# cave.net
KiCad netlist of a schematic drawn in EAGLE
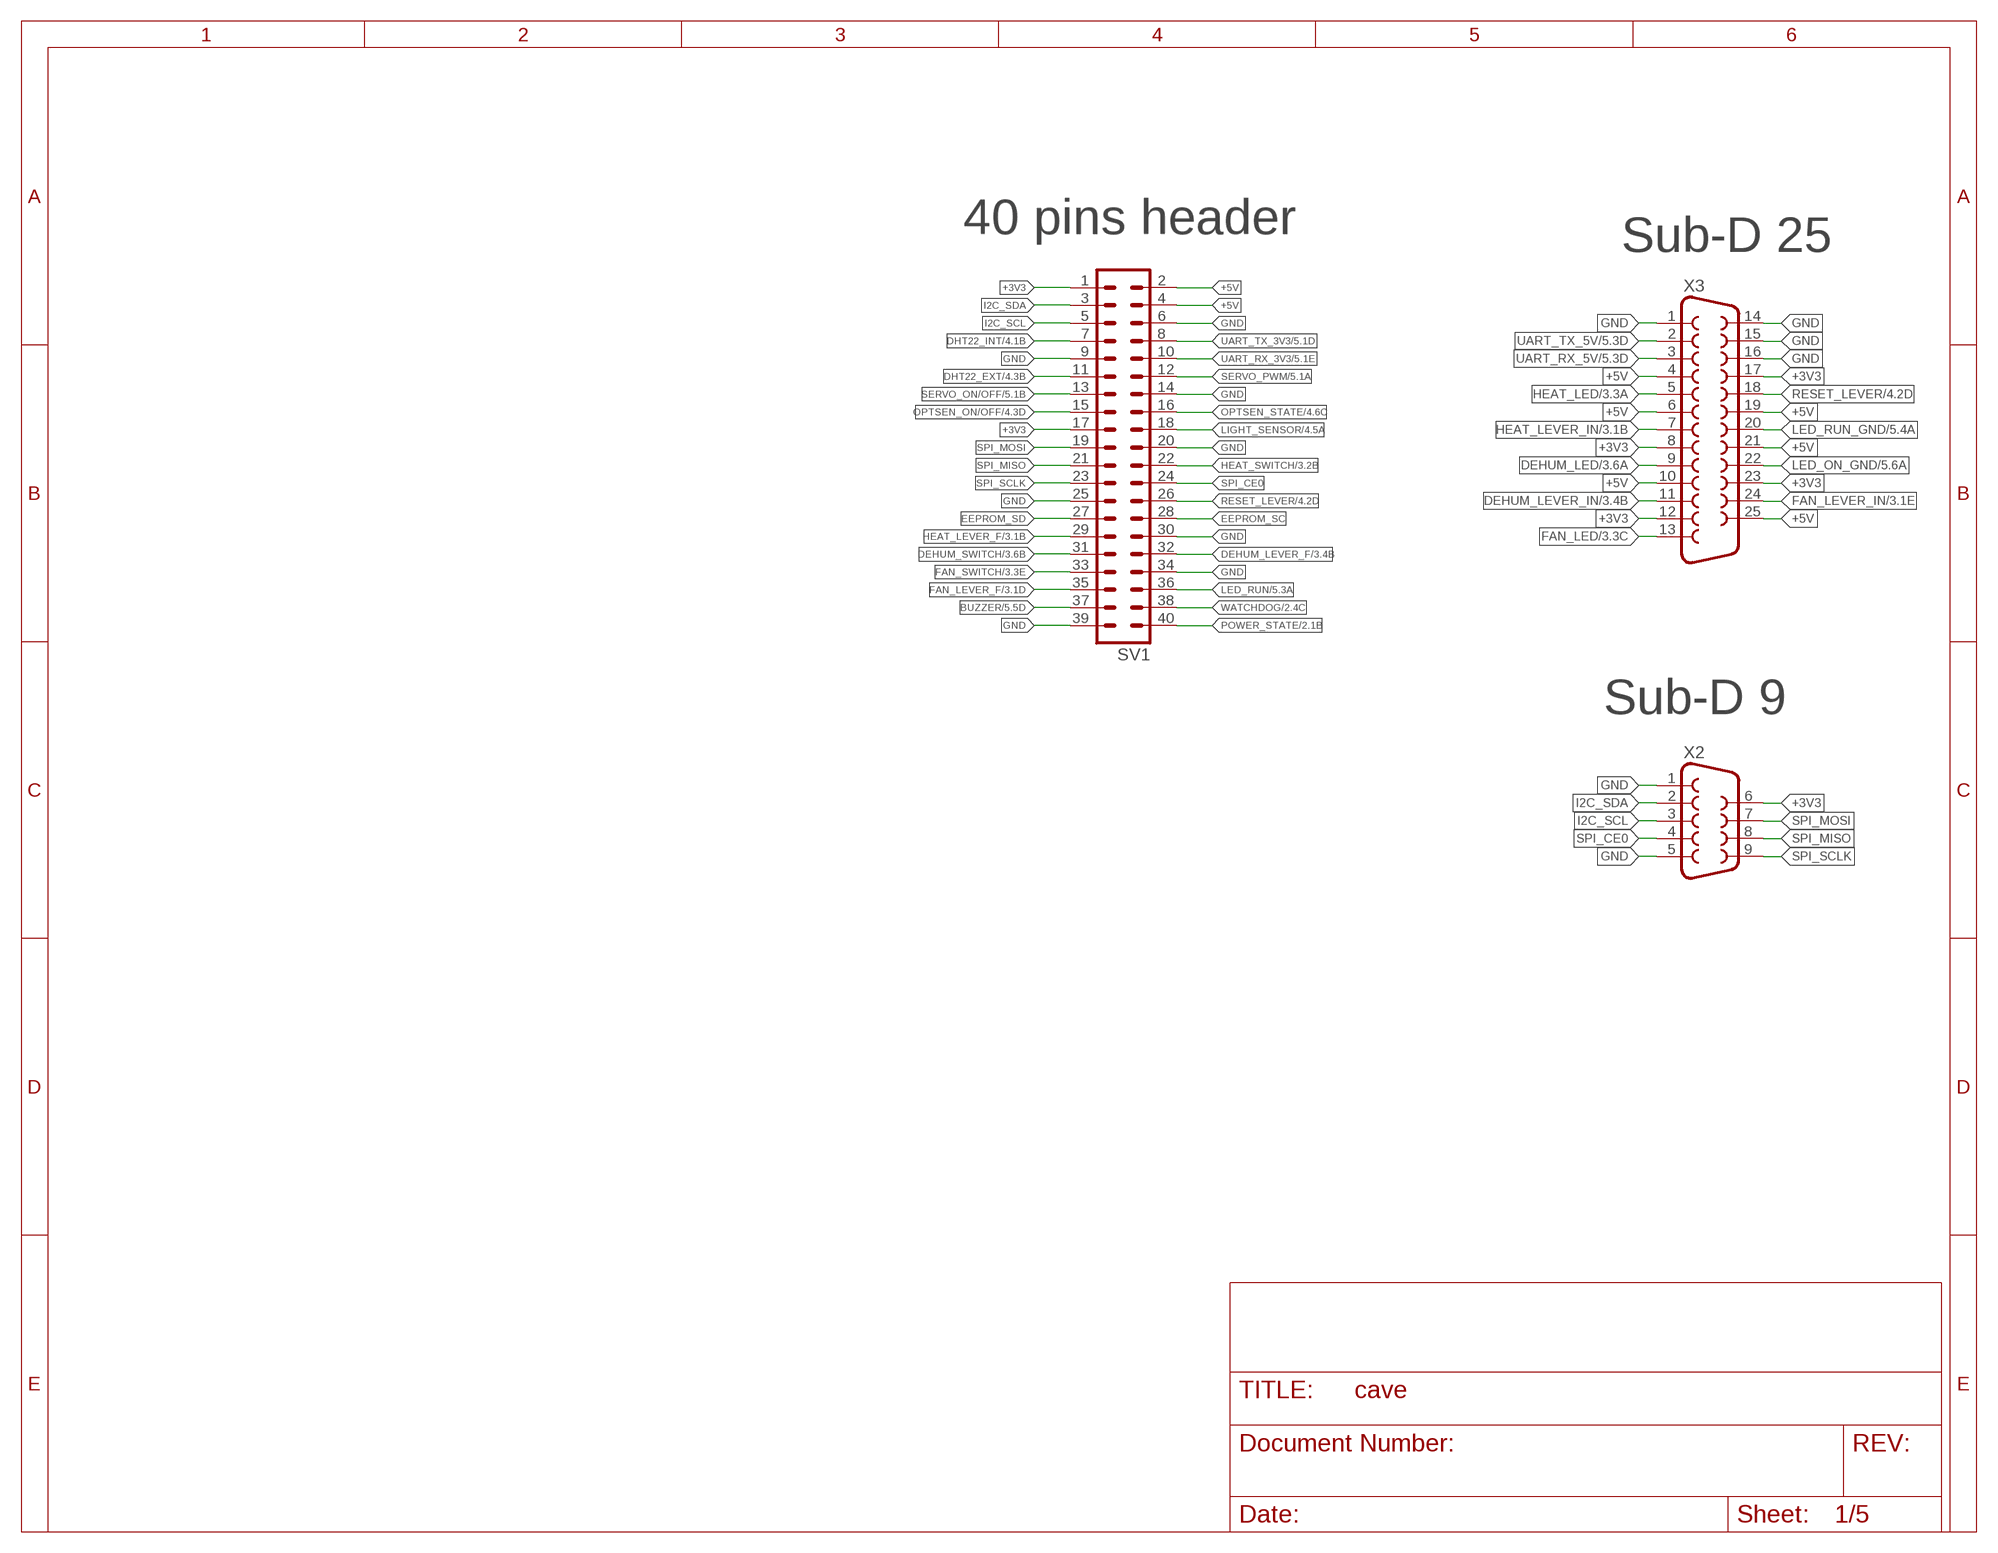
[diagram p0: schematic, sheet 1]
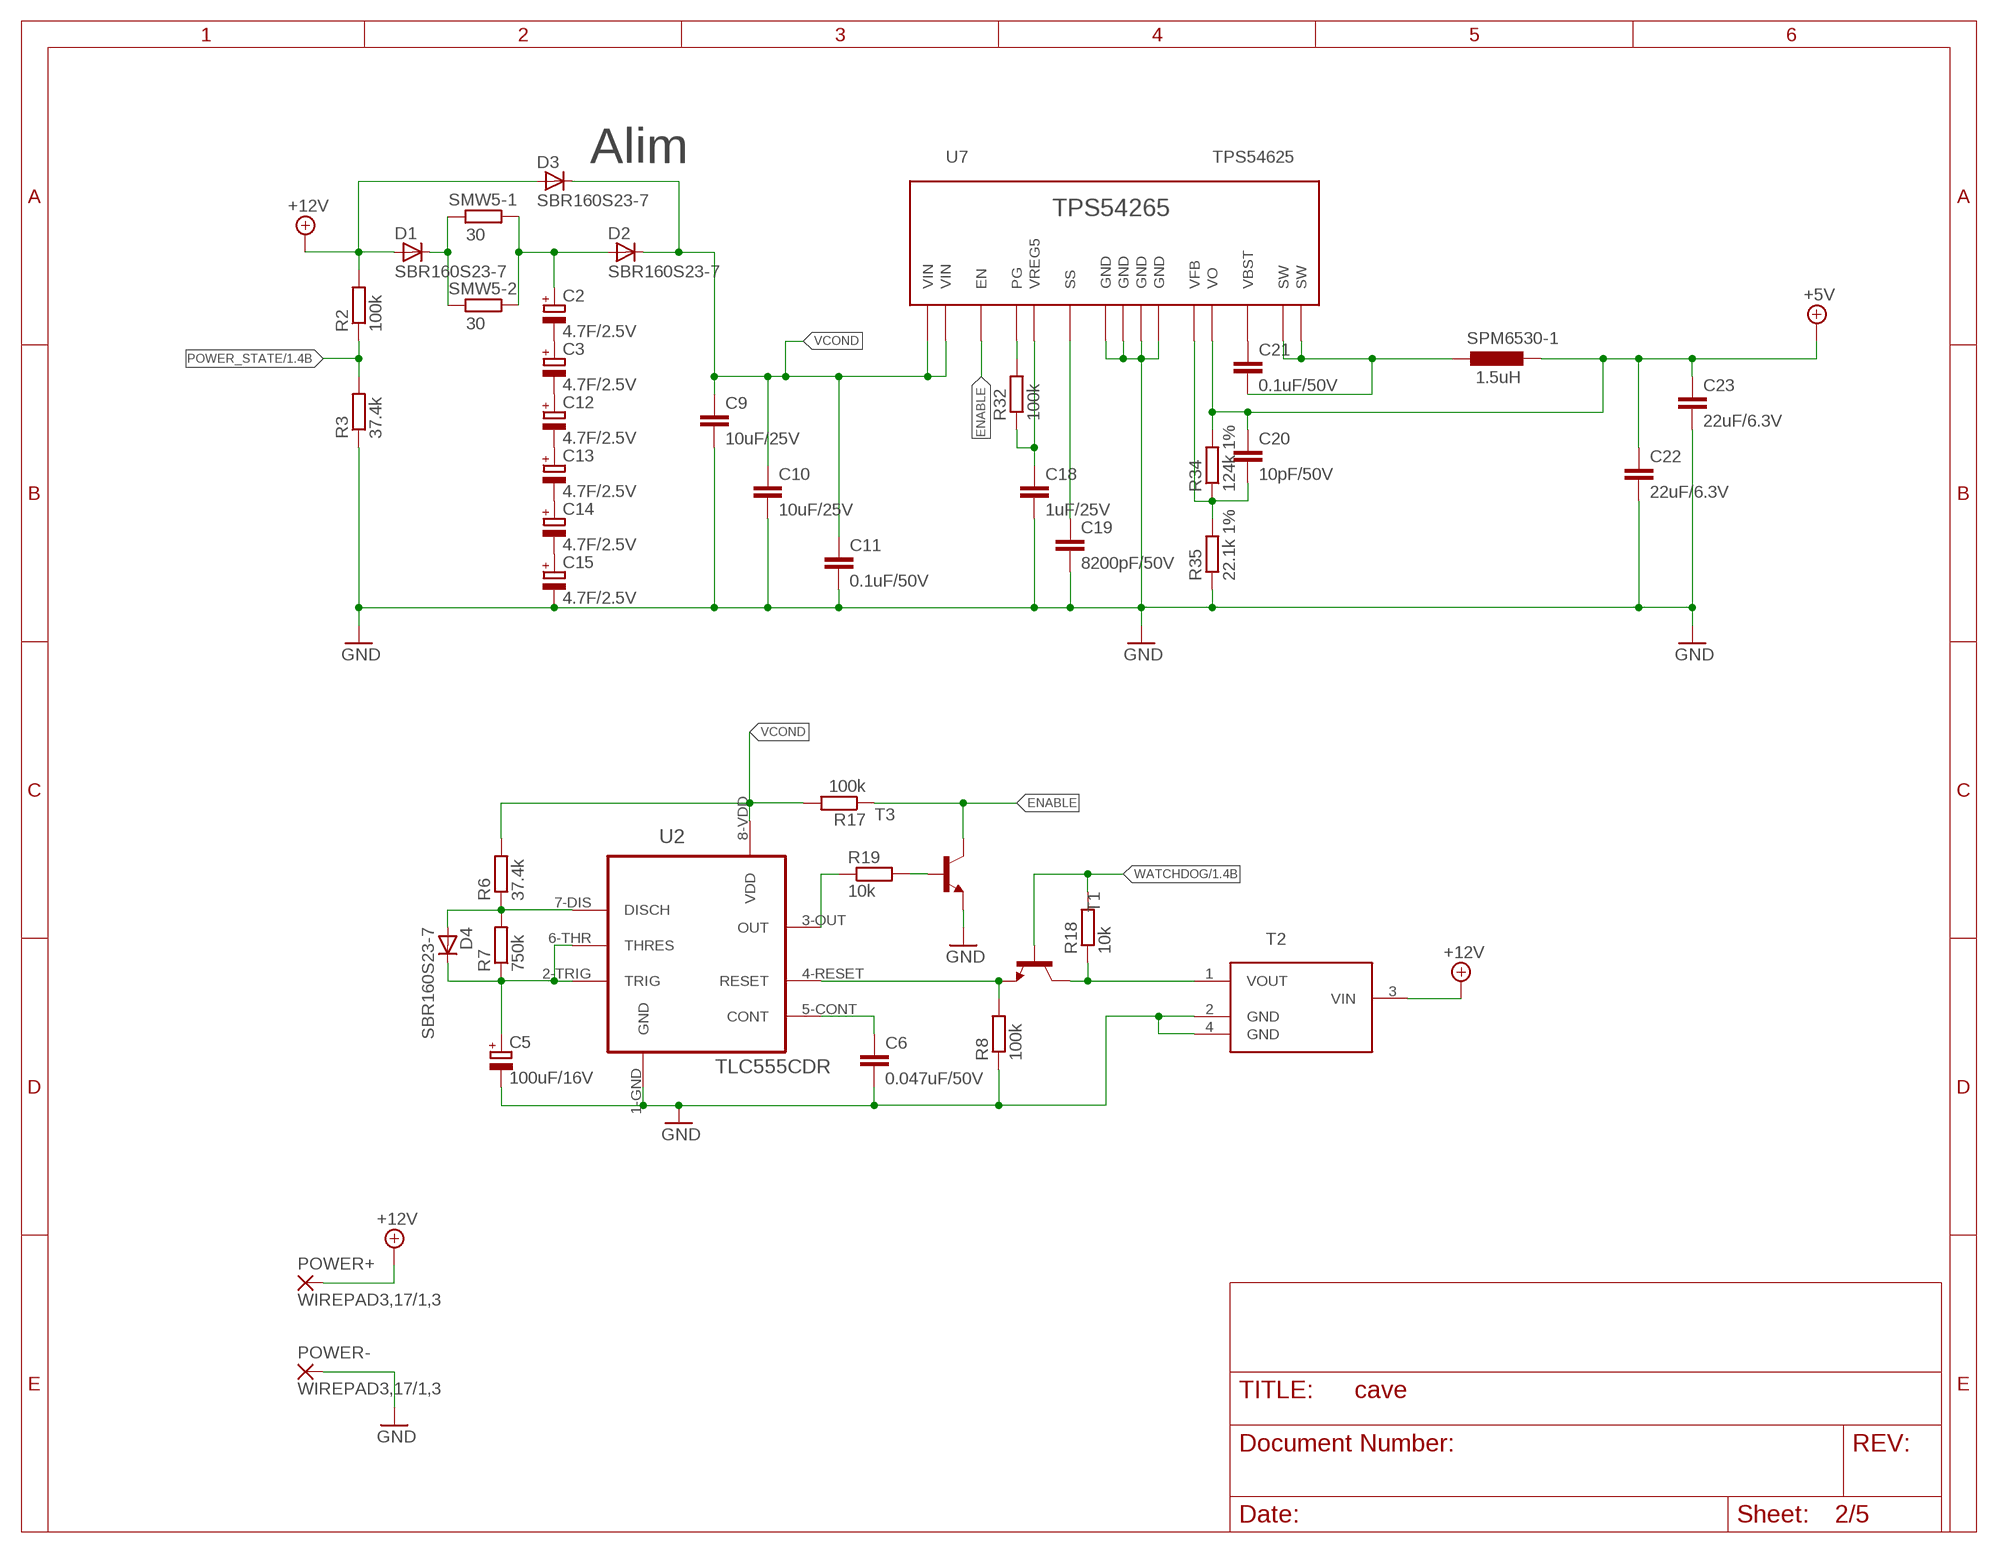
[diagram p1: schematic, sheet 2]
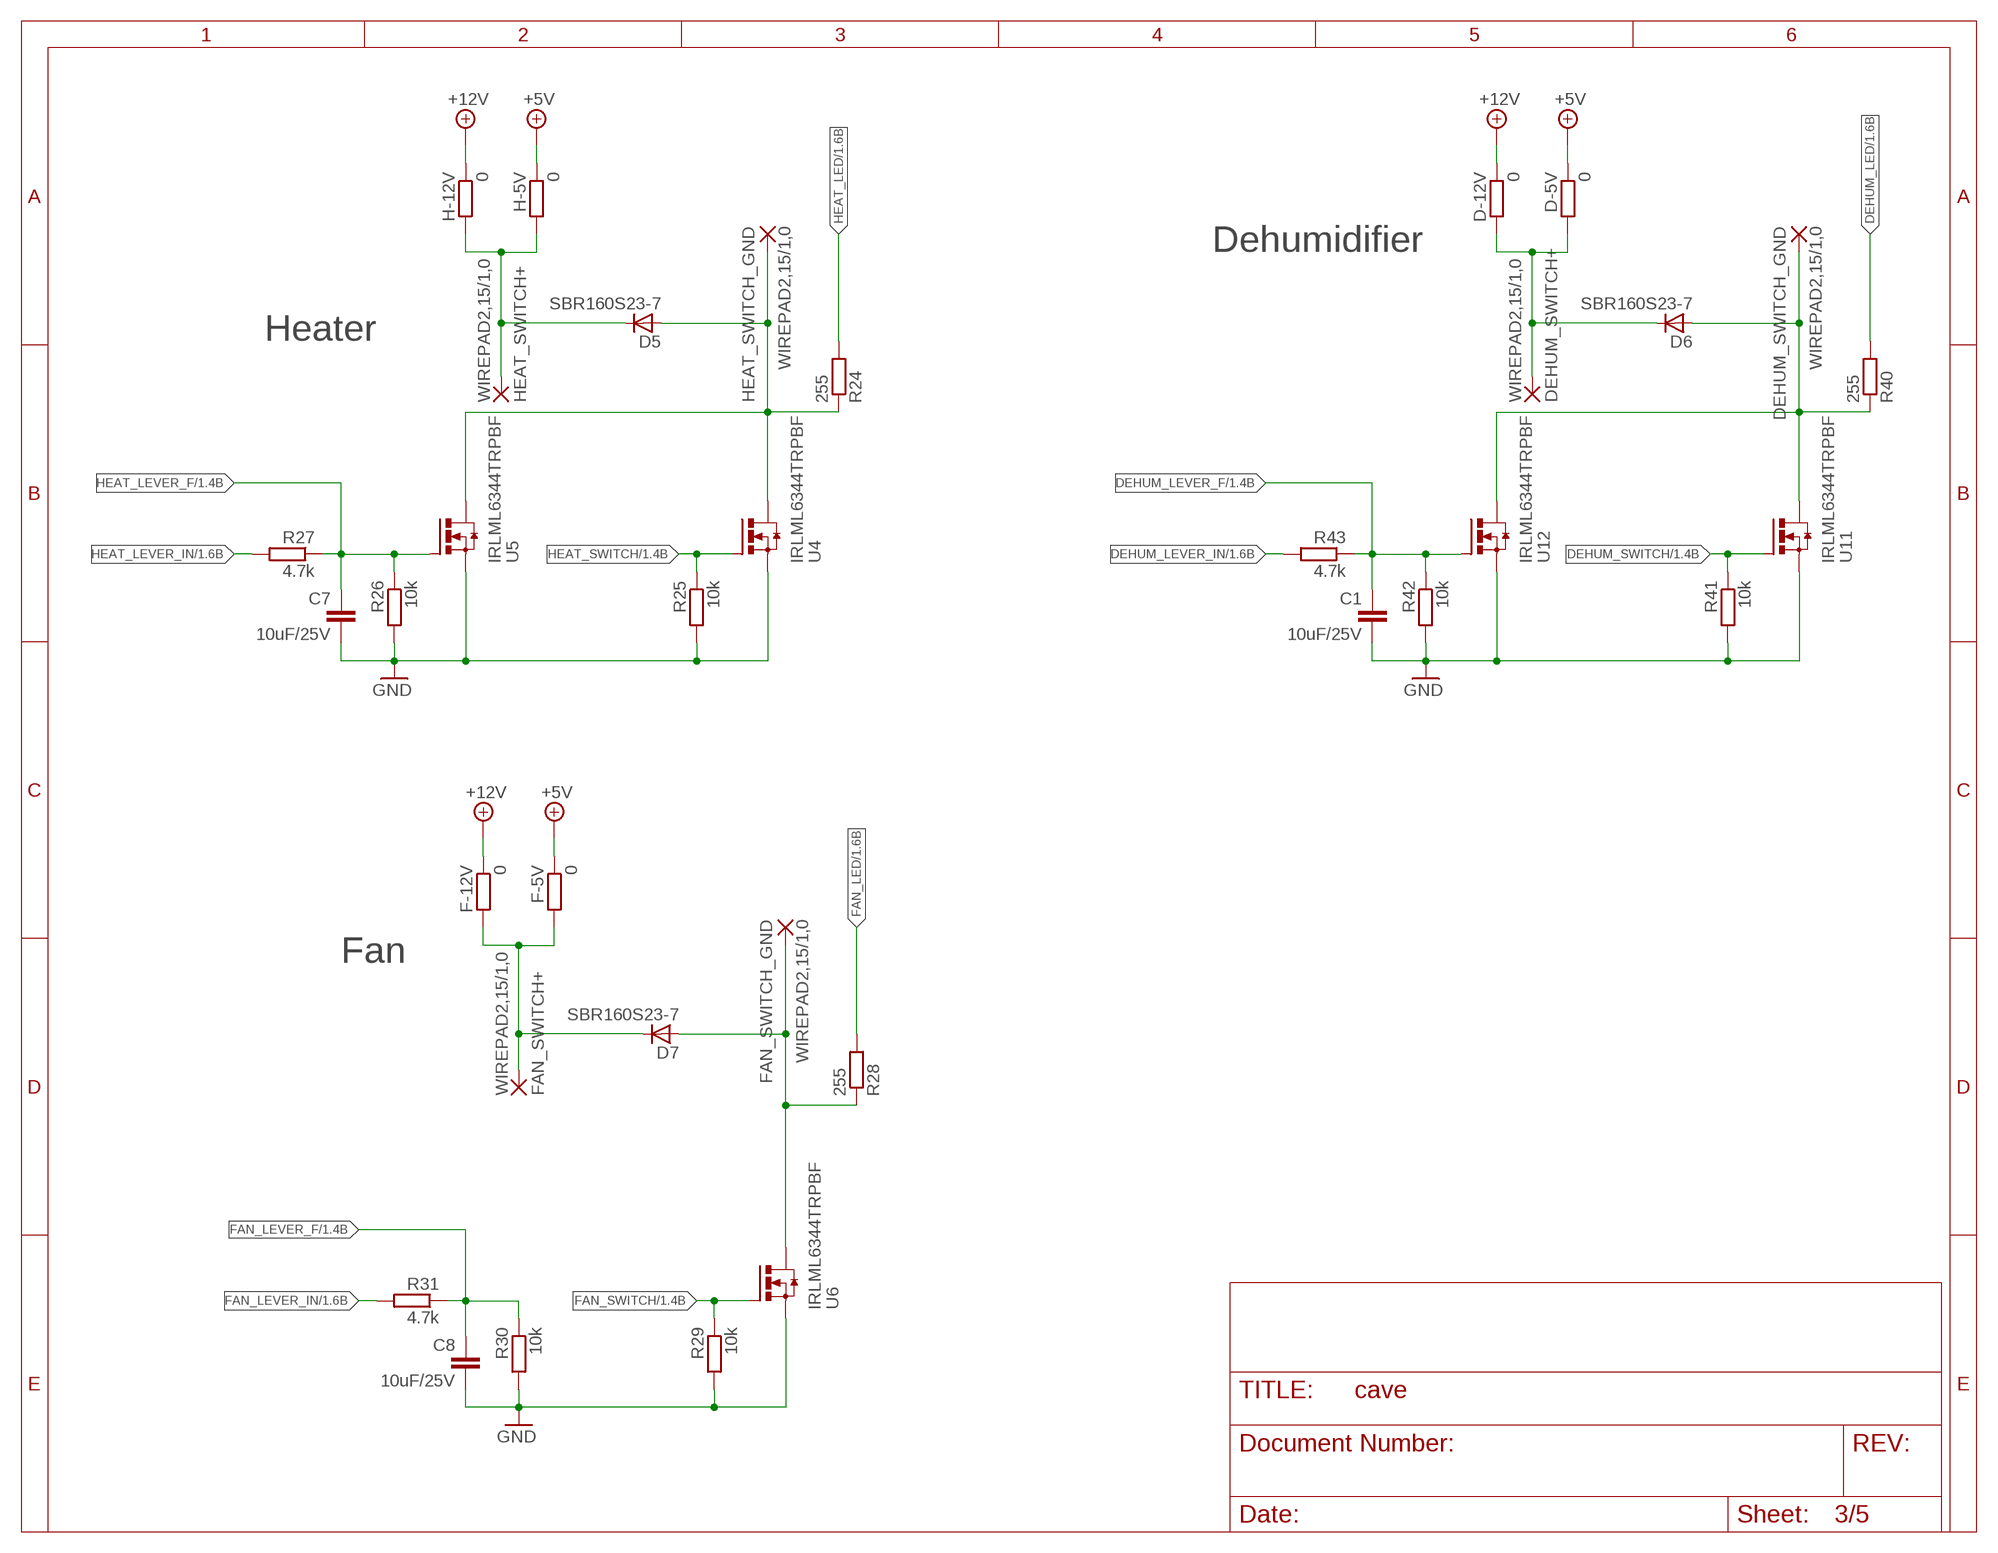
[diagram p2: schematic, sheet 3]
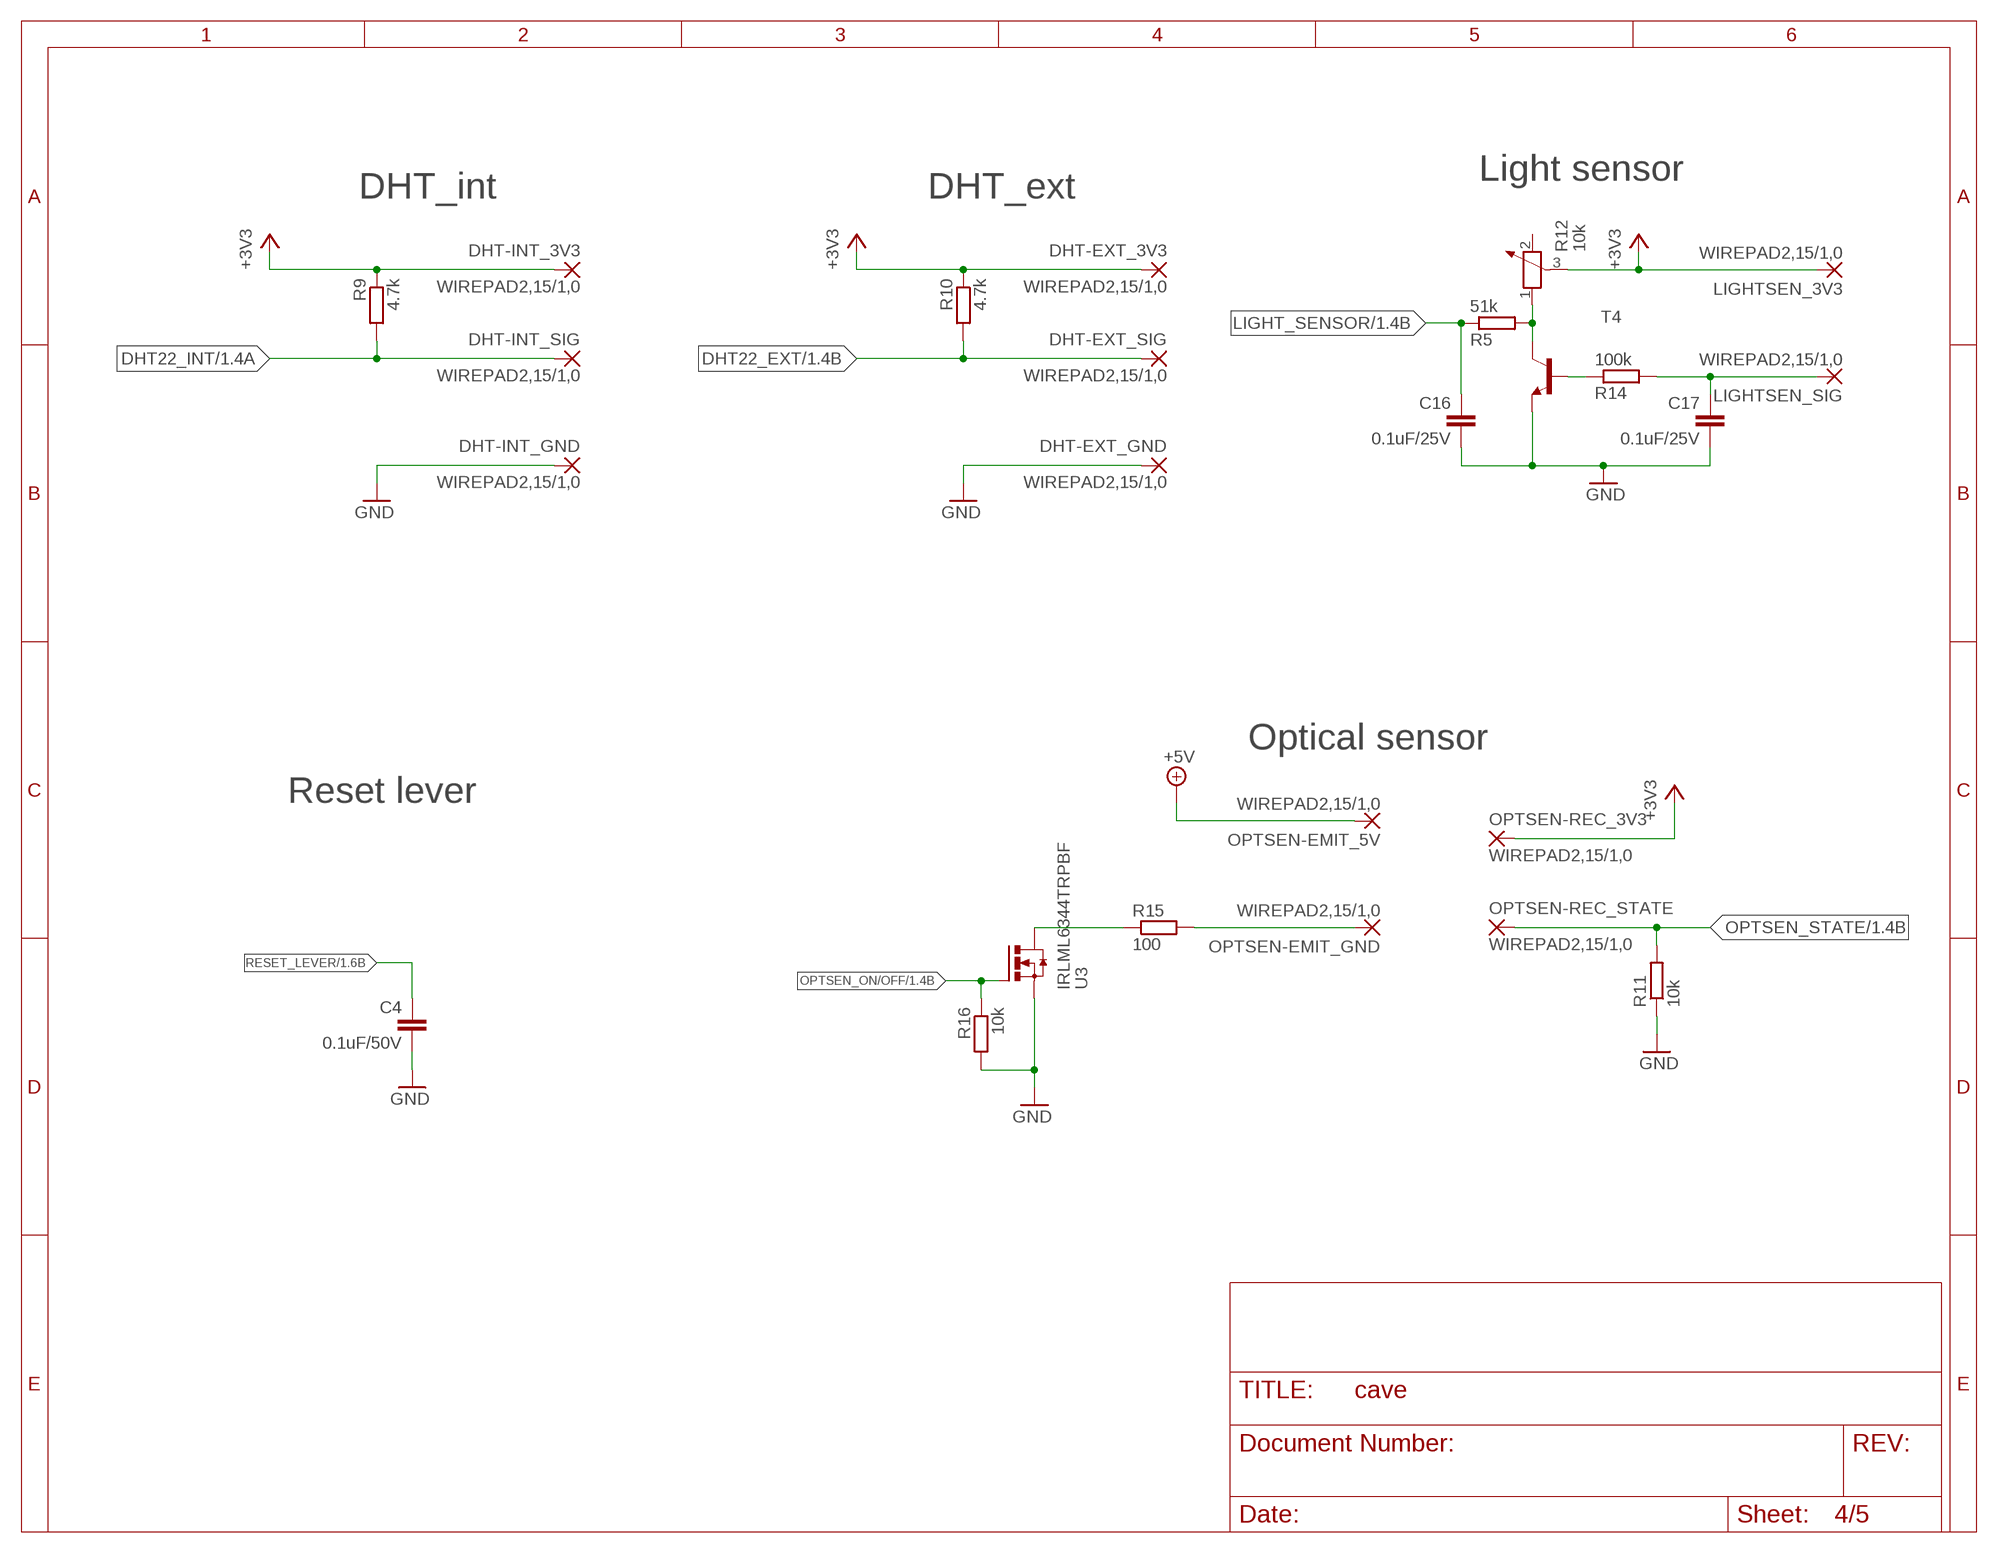
[diagram p3: schematic, sheet 4]
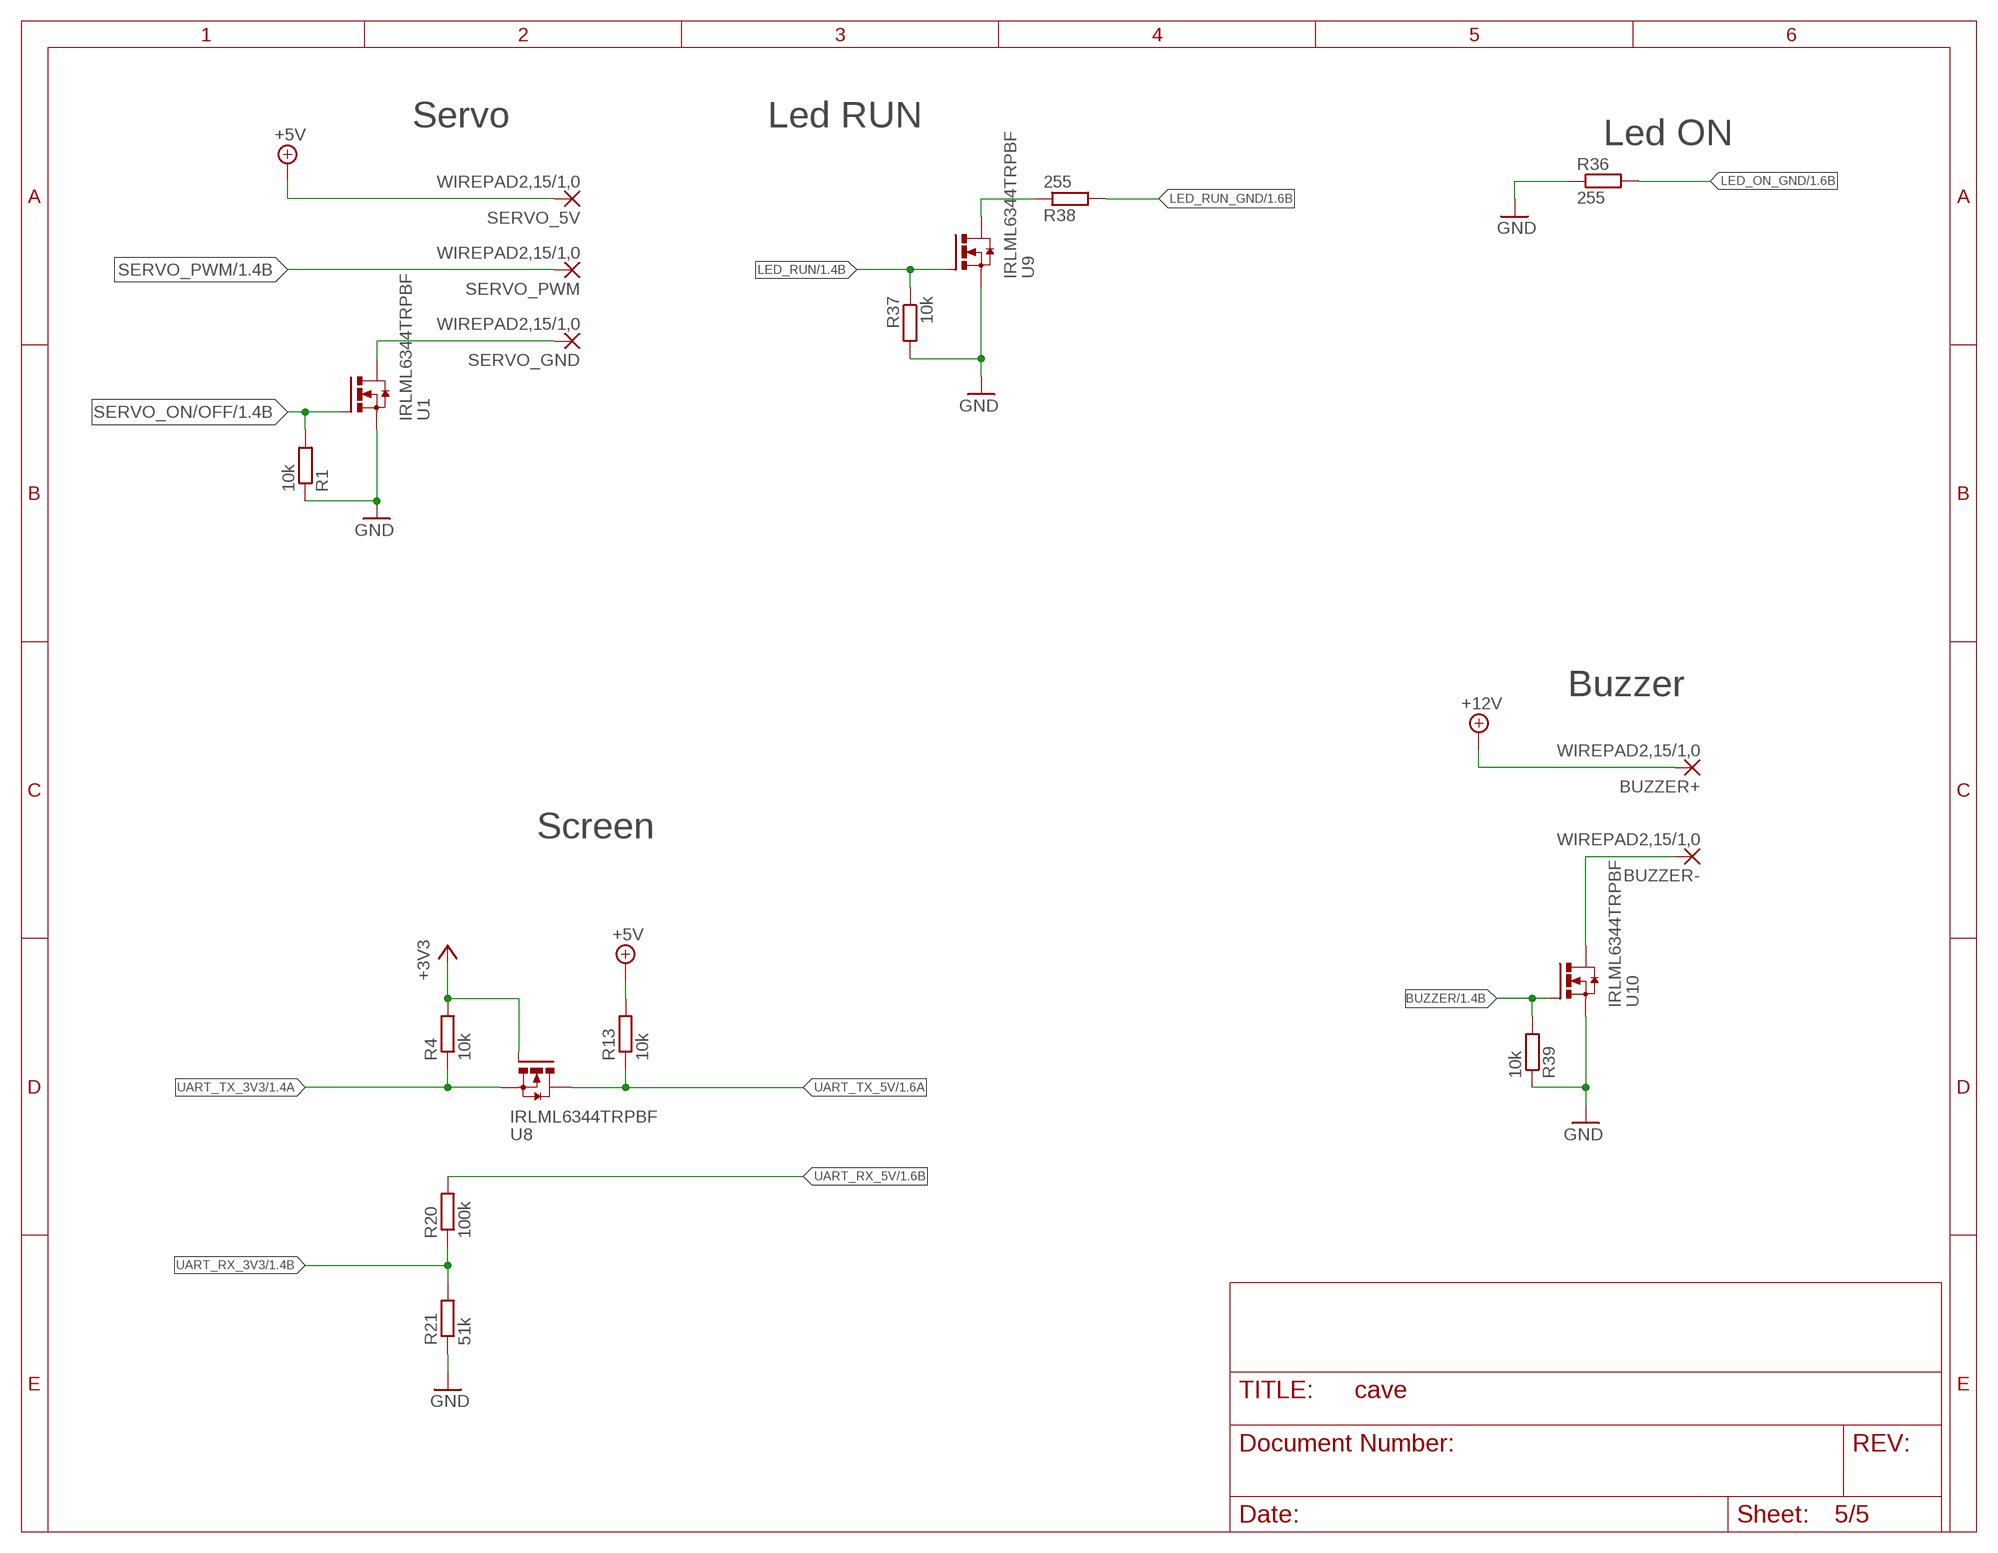
[diagram p4: schematic, sheet 5]

(export (version "E")
  (design (tool "Eeschema 10.0.6"))
  (components
    (comp (ref "C2")
      (value "4.7F/2.5V")
      (footprint "eagle-import:E5-10,5")
      (libsource (lib "eagle-import") (part "CPOL-EUE5-10.5"))
    )
    (comp (ref "C3")
      (value "4.7F/2.5V")
      (footprint "eagle-import:E5-10,5")
      (libsource (lib "eagle-import") (part "CPOL-EUE5-10.5"))
    )
    (comp (ref "C5")
      (value "100uF/16V")
      (footprint "eagle-import:D_7343-31W")
      (libsource (lib "eagle-import") (part "resistor_CPOL-EUD/7343-31W"))
    )
    (comp (ref "C6")
      (value "0.047uF/50V")
      (footprint "eagle-import:C0603")
      (libsource (lib "eagle-import") (part "C-EUC0603"))
    )
    (comp (ref "C9")
      (value "10uF/25V")
      (footprint "eagle-import:C0805")
      (libsource (lib "eagle-import") (part "C-EUC0805"))
    )
    (comp (ref "C10")
      (value "10uF/25V")
      (footprint "eagle-import:C0805")
      (libsource (lib "eagle-import") (part "C-EUC0805"))
    )
    (comp (ref "C11")
      (value "0.1uF/50V")
      (footprint "eagle-import:C0603")
      (libsource (lib "eagle-import") (part "C-EUC0603"))
    )
    (comp (ref "C12")
      (value "4.7F/2.5V")
      (footprint "eagle-import:E5-10,5")
      (libsource (lib "eagle-import") (part "CPOL-EUE5-10.5"))
    )
    (comp (ref "C13")
      (value "4.7F/2.5V")
      (footprint "eagle-import:E5-10,5")
      (libsource (lib "eagle-import") (part "CPOL-EUE5-10.5"))
    )
    (comp (ref "C14")
      (value "4.7F/2.5V")
      (footprint "eagle-import:E5-10,5")
      (libsource (lib "eagle-import") (part "CPOL-EUE5-10.5"))
    )
    (comp (ref "C15")
      (value "4.7F/2.5V")
      (footprint "eagle-import:E5-10,5")
      (libsource (lib "eagle-import") (part "CPOL-EUE5-10.5"))
    )
    (comp (ref "C18")
      (value "1uF/25V")
      (footprint "eagle-import:C0603")
      (libsource (lib "eagle-import") (part "C-EUC0603"))
    )
    (comp (ref "C19")
      (value "8200pF/50V")
      (footprint "eagle-import:C0603")
      (libsource (lib "eagle-import") (part "C-EUC0603"))
    )
    (comp (ref "C20")
      (value "10pF/50V")
      (footprint "eagle-import:C0603")
      (libsource (lib "eagle-import") (part "C-EUC0603"))
    )
    (comp (ref "C21")
      (value "0.1uF/50V")
      (footprint "eagle-import:C0603")
      (libsource (lib "eagle-import") (part "C-EUC0603"))
    )
    (comp (ref "C22")
      (value "22uF/6.3V")
      (footprint "eagle-import:C0805")
      (libsource (lib "eagle-import") (part "C-EUC0805"))
    )
    (comp (ref "C23")
      (value "22uF/6.3V")
      (footprint "eagle-import:C0805")
      (libsource (lib "eagle-import") (part "C-EUC0805"))
    )
    (comp (ref "D1")
      (value "SBR160S23-7")
      (footprint "eagle-import:SOT23")
      (libsource (lib "eagle-import") (part "D-A1-C3"))
    )
    (comp (ref "D2")
      (value "SBR160S23-7")
      (footprint "eagle-import:SOT23")
      (libsource (lib "eagle-import") (part "D-A1-C3"))
    )
    (comp (ref "D3")
      (value "SBR160S23-7")
      (footprint "eagle-import:SOT23")
      (libsource (lib "eagle-import") (part "D-A1-C3"))
    )
    (comp (ref "D4")
      (value "SBR160S23-7")
      (footprint "eagle-import:SOT23")
      (libsource (lib "eagle-import") (part "D-A1-C3"))
    )
    (comp (ref "POWER+")
      (value "WIREPAD3,17/1,3")
      (footprint "eagle-import:3,17_1,3")
      (libsource (lib "eagle-import") (part "WIREPAD3,17/1,3"))
    )
    (comp (ref "POWER-")
      (value "WIREPAD3,17/1,3")
      (footprint "eagle-import:3,17_1,3")
      (libsource (lib "eagle-import") (part "WIREPAD3,17/1,3"))
    )
    (comp (ref "R2")
      (value "100k")
      (footprint "eagle-import:R0603")
      (libsource (lib "eagle-import") (part "R-EU_R0603"))
    )
    (comp (ref "R3")
      (value "37.4k")
      (footprint "eagle-import:R0603")
      (libsource (lib "eagle-import") (part "R-EU_R0603"))
    )
    (comp (ref "R6")
      (value "37.4k")
      (footprint "eagle-import:R0603")
      (libsource (lib "eagle-import") (part "R-EU_R0603"))
    )
    (comp (ref "R7")
      (value "750k")
      (footprint "eagle-import:R0603")
      (libsource (lib "eagle-import") (part "R-EU_R0603"))
    )
    (comp (ref "R8")
      (value "100k")
      (footprint "eagle-import:R0603")
      (libsource (lib "eagle-import") (part "R-EU_R0603"))
    )
    (comp (ref "R17")
      (value "100k")
      (footprint "eagle-import:R0603")
      (libsource (lib "eagle-import") (part "R-EU_R0603"))
    )
    (comp (ref "R18")
      (value "10k")
      (footprint "eagle-import:R0603")
      (libsource (lib "eagle-import") (part "R-EU_R0603"))
    )
    (comp (ref "R19")
      (value "10k")
      (footprint "eagle-import:R0603")
      (libsource (lib "eagle-import") (part "R-EU_R0603"))
    )
    (comp (ref "R32")
      (value "100k")
      (footprint "eagle-import:R0603")
      (libsource (lib "eagle-import") (part "R-EU_R0603"))
    )
    (comp (ref "R34")
      (value "124k 1%")
      (footprint "eagle-import:R0603")
      (libsource (lib "eagle-import") (part "R-EU_R0603"))
    )
    (comp (ref "R35")
      (value "22.1k 1%")
      (footprint "eagle-import:R0603")
      (libsource (lib "eagle-import") (part "R-EU_R0603"))
    )
    (comp (ref "SMW5-1")
      (value "30")
      (footprint "eagle-import:SM_5")
      (libsource (lib "eagle-import") (part "SMW530RJT"))
    )
    (comp (ref "SMW5-2")
      (value "30")
      (footprint "eagle-import:SM_5")
      (libsource (lib "eagle-import") (part "SMW530RJT"))
    )
    (comp (ref "SPM6530-1")
      (value "1.5uH")
      (footprint "eagle-import:6530")
      (libsource (lib "eagle-import") (part "SPM6530"))
    )
    (comp (ref "T1")
      (value "MMBT2369LT1-NPN-SOT23-BEC")
      (footprint "eagle-import:SOT23-BEC")
      (libsource (lib "eagle-import") (part "-NPN-SOT23-BECMMBT2369LT1"))
    )
    (comp (ref "T2")
      (value "L78L33ACUTR")
      (footprint "eagle-import:SOT150P400X160-4N")
      (libsource (lib "eagle-import") (part "L78L33ACUTR"))
    )
    (comp (ref "T3")
      (value "MMBT2369LT1-NPN-SOT23-BEC")
      (footprint "eagle-import:SOT23-BEC")
      (libsource (lib "eagle-import") (part "-NPN-SOT23-BECMMBT2369LT1"))
    )
    (comp (ref "U2")
      (value "TLC555CDR")
      (footprint "eagle-import:SOIC127P600X175-8N")
      (libsource (lib "eagle-import") (part "TLC555CDR"))
    )
    (comp (ref "U7")
      (value "TPS54625")
      (footprint "eagle-import:HTSSOP-14")
      (libsource (lib "eagle-import") (part "TPS54625"))
    )
    (comp (ref "C4")
      (value "0.1uF/50V")
      (footprint "eagle-import:C0603")
      (libsource (lib "eagle-import") (part "C-EUC0603"))
    )
    (comp (ref "C16")
      (value "0.1uF/25V")
      (footprint "eagle-import:C0603")
      (libsource (lib "eagle-import") (part "C-EUC0603"))
    )
    (comp (ref "C17")
      (value "0.1uF/25V")
      (footprint "eagle-import:C0603")
      (libsource (lib "eagle-import") (part "C-EUC0603"))
    )
    (comp (ref "DHT-EXT_3V3")
      (value "WIREPAD2,15/1,0")
      (footprint "eagle-import:2,15_1,0")
      (libsource (lib "eagle-import") (part "WIREPAD2,15/1,0"))
    )
    (comp (ref "DHT-EXT_GND")
      (value "WIREPAD2,15/1,0")
      (footprint "eagle-import:2,15_1,0")
      (libsource (lib "eagle-import") (part "WIREPAD2,15/1,0"))
    )
    (comp (ref "DHT-EXT_SIG")
      (value "WIREPAD2,15/1,0")
      (footprint "eagle-import:2,15_1,0")
      (libsource (lib "eagle-import") (part "WIREPAD2,15/1,0"))
    )
    (comp (ref "DHT-INT_3V3")
      (value "WIREPAD2,15/1,0")
      (footprint "eagle-import:2,15_1,0")
      (libsource (lib "eagle-import") (part "WIREPAD2,15/1,0"))
    )
    (comp (ref "DHT-INT_GND")
      (value "WIREPAD2,15/1,0")
      (footprint "eagle-import:2,15_1,0")
      (libsource (lib "eagle-import") (part "WIREPAD2,15/1,0"))
    )
    (comp (ref "DHT-INT_SIG")
      (value "WIREPAD2,15/1,0")
      (footprint "eagle-import:2,15_1,0")
      (libsource (lib "eagle-import") (part "WIREPAD2,15/1,0"))
    )
    (comp (ref "LIGHTSEN_3V3")
      (value "WIREPAD2,15/1,0")
      (footprint "eagle-import:2,15_1,0")
      (libsource (lib "eagle-import") (part "WIREPAD2,15/1,0"))
    )
    (comp (ref "LIGHTSEN_SIG")
      (value "WIREPAD2,15/1,0")
      (footprint "eagle-import:2,15_1,0")
      (libsource (lib "eagle-import") (part "WIREPAD2,15/1,0"))
    )
    (comp (ref "OPTSEN-EMIT_5V")
      (value "WIREPAD2,15/1,0")
      (footprint "eagle-import:2,15_1,0")
      (libsource (lib "eagle-import") (part "WIREPAD2,15/1,0"))
    )
    (comp (ref "OPTSEN-EMIT_GND")
      (value "WIREPAD2,15/1,0")
      (footprint "eagle-import:2,15_1,0")
      (libsource (lib "eagle-import") (part "WIREPAD2,15/1,0"))
    )
    (comp (ref "OPTSEN-REC_3V3")
      (value "WIREPAD2,15/1,0")
      (footprint "eagle-import:2,15_1,0")
      (libsource (lib "eagle-import") (part "WIREPAD2,15/1,0"))
    )
    (comp (ref "OPTSEN-REC_STATE")
      (value "WIREPAD2,15/1,0")
      (footprint "eagle-import:2,15_1,0")
      (libsource (lib "eagle-import") (part "WIREPAD2,15/1,0"))
    )
    (comp (ref "R5")
      (value "51k")
      (footprint "eagle-import:R0603")
      (libsource (lib "eagle-import") (part "R-EU_R0603"))
    )
    (comp (ref "R9")
      (value "4.7k")
      (footprint "eagle-import:R0603")
      (libsource (lib "eagle-import") (part "R-EU_R0603"))
    )
    (comp (ref "R10")
      (value "4.7k")
      (footprint "eagle-import:R0603")
      (libsource (lib "eagle-import") (part "R-EU_R0603"))
    )
    (comp (ref "R11")
      (value "10k")
      (footprint "eagle-import:R0603")
      (libsource (lib "eagle-import") (part "R-EU_R0603"))
    )
    (comp (ref "R12")
      (value "10k")
      (footprint "eagle-import:PT-SPIN")
      (libsource (lib "eagle-import") (part "POTENTIOMETER_PT_SPIN"))
    )
    (comp (ref "R14")
      (value "100k")
      (footprint "eagle-import:R0603")
      (libsource (lib "eagle-import") (part "R-EU_R0603"))
    )
    (comp (ref "R15")
      (value "100")
      (footprint "eagle-import:R0805")
      (libsource (lib "eagle-import") (part "R-EU_R0805"))
    )
    (comp (ref "R16")
      (value "10k")
      (footprint "eagle-import:R0603")
      (libsource (lib "eagle-import") (part "R-EU_R0603"))
    )
    (comp (ref "T4")
      (value "MMBT2369LT1-NPN-SOT23-BEC")
      (footprint "eagle-import:SOT23-BEC")
      (libsource (lib "eagle-import") (part "-NPN-SOT23-BECMMBT2369LT1"))
    )
    (comp (ref "U3")
      (value "IRLML6344TRPBF")
      (footprint "eagle-import:SOT95P240X112-3N")
      (libsource (lib "eagle-import") (part "IRLML6344TRPBF"))
    )
    (comp (ref "SV1")
      (value "MA20-2")
      (footprint "eagle-import:MA20-2")
      (libsource (lib "eagle-import") (part "MA20-2"))
    )
    (comp (ref "X2")
      (value "F09V")
      (footprint "eagle-import:F09V")
      (libsource (lib "eagle-import") (part "F09V"))
    )
    (comp (ref "X3")
      (value "F25V")
      (footprint "eagle-import:F25V")
      (libsource (lib "eagle-import") (part "F25V"))
    )
    (comp (ref "BUZZER+")
      (value "WIREPAD2,15/1,0")
      (footprint "eagle-import:2,15_1,0")
      (libsource (lib "eagle-import") (part "WIREPAD2,15/1,0"))
    )
    (comp (ref "BUZZER-")
      (value "WIREPAD2,15/1,0")
      (footprint "eagle-import:2,15_1,0")
      (libsource (lib "eagle-import") (part "WIREPAD2,15/1,0"))
    )
    (comp (ref "R1")
      (value "10k")
      (footprint "eagle-import:R0603")
      (libsource (lib "eagle-import") (part "R-EU_R0603"))
    )
    (comp (ref "R4")
      (value "10k")
      (footprint "eagle-import:R0603")
      (libsource (lib "eagle-import") (part "R-EU_R0603"))
    )
    (comp (ref "R13")
      (value "10k")
      (footprint "eagle-import:R0603")
      (libsource (lib "eagle-import") (part "R-EU_R0603"))
    )
    (comp (ref "R20")
      (value "100k")
      (footprint "eagle-import:R0603")
      (libsource (lib "eagle-import") (part "R-EU_R0603"))
    )
    (comp (ref "R21")
      (value "51k")
      (footprint "eagle-import:R0603")
      (libsource (lib "eagle-import") (part "R-EU_R0603"))
    )
    (comp (ref "R36")
      (value "255")
      (footprint "eagle-import:R0805")
      (libsource (lib "eagle-import") (part "R-EU_R0805"))
    )
    (comp (ref "R37")
      (value "10k")
      (footprint "eagle-import:R0603")
      (libsource (lib "eagle-import") (part "R-EU_R0603"))
    )
    (comp (ref "R38")
      (value "255")
      (footprint "eagle-import:R0805")
      (libsource (lib "eagle-import") (part "R-EU_R0805"))
    )
    (comp (ref "R39")
      (value "10k")
      (footprint "eagle-import:R0603")
      (libsource (lib "eagle-import") (part "R-EU_R0603"))
    )
    (comp (ref "SERVO_5V")
      (value "WIREPAD2,15/1,0")
      (footprint "eagle-import:2,15_1,0")
      (libsource (lib "eagle-import") (part "WIREPAD2,15/1,0"))
    )
    (comp (ref "SERVO_GND")
      (value "WIREPAD2,15/1,0")
      (footprint "eagle-import:2,15_1,0")
      (libsource (lib "eagle-import") (part "WIREPAD2,15/1,0"))
    )
    (comp (ref "SERVO_PWM")
      (value "WIREPAD2,15/1,0")
      (footprint "eagle-import:2,15_1,0")
      (libsource (lib "eagle-import") (part "WIREPAD2,15/1,0"))
    )
    (comp (ref "U1")
      (value "IRLML6344TRPBF")
      (footprint "eagle-import:SOT95P240X112-3N")
      (libsource (lib "eagle-import") (part "IRLML6344TRPBF"))
    )
    (comp (ref "U8")
      (value "IRLML6344TRPBF")
      (footprint "eagle-import:SOT95P240X112-3N")
      (libsource (lib "eagle-import") (part "IRLML6344TRPBF"))
    )
    (comp (ref "U9")
      (value "IRLML6344TRPBF")
      (footprint "eagle-import:SOT95P240X112-3N")
      (libsource (lib "eagle-import") (part "IRLML6344TRPBF"))
    )
    (comp (ref "U10")
      (value "IRLML6344TRPBF")
      (footprint "eagle-import:SOT95P240X112-3N")
      (libsource (lib "eagle-import") (part "IRLML6344TRPBF"))
    )
    (comp (ref "C1")
      (value "10uF/25V")
      (footprint "eagle-import:C0805")
      (libsource (lib "eagle-import") (part "C-EUC0805"))
    )
    (comp (ref "C7")
      (value "10uF/25V")
      (footprint "eagle-import:C0805")
      (libsource (lib "eagle-import") (part "C-EUC0805"))
    )
    (comp (ref "C8")
      (value "10uF/25V")
      (footprint "eagle-import:C0805")
      (libsource (lib "eagle-import") (part "C-EUC0805"))
    )
    (comp (ref "D-5V")
      (value "0")
      (footprint "eagle-import:R0805")
      (libsource (lib "eagle-import") (part "R-EU_R0805"))
    )
    (comp (ref "D-12V")
      (value "0")
      (footprint "eagle-import:R0805")
      (libsource (lib "eagle-import") (part "R-EU_R0805"))
    )
    (comp (ref "D5")
      (value "SBR160S23-7")
      (footprint "eagle-import:SOT23")
      (libsource (lib "eagle-import") (part "D-A1-C3"))
    )
    (comp (ref "D6")
      (value "SBR160S23-7")
      (footprint "eagle-import:SOT23")
      (libsource (lib "eagle-import") (part "D-A1-C3"))
    )
    (comp (ref "D7")
      (value "SBR160S23-7")
      (footprint "eagle-import:SOT23")
      (libsource (lib "eagle-import") (part "D-A1-C3"))
    )
    (comp (ref "DEHUM_SWITCH+")
      (value "WIREPAD2,15/1,0")
      (footprint "eagle-import:2,15_1,0")
      (libsource (lib "eagle-import") (part "WIREPAD2,15/1,0"))
    )
    (comp (ref "DEHUM_SWITCH_GND")
      (value "WIREPAD2,15/1,0")
      (footprint "eagle-import:2,15_1,0")
      (libsource (lib "eagle-import") (part "WIREPAD2,15/1,0"))
    )
    (comp (ref "F-5V")
      (value "0")
      (footprint "eagle-import:R0805")
      (libsource (lib "eagle-import") (part "R-EU_R0805"))
    )
    (comp (ref "F-12V")
      (value "0")
      (footprint "eagle-import:R0805")
      (libsource (lib "eagle-import") (part "R-EU_R0805"))
    )
    (comp (ref "FAN_SWITCH+")
      (value "WIREPAD2,15/1,0")
      (footprint "eagle-import:2,15_1,0")
      (libsource (lib "eagle-import") (part "WIREPAD2,15/1,0"))
    )
    (comp (ref "FAN_SWITCH_GND")
      (value "WIREPAD2,15/1,0")
      (footprint "eagle-import:2,15_1,0")
      (libsource (lib "eagle-import") (part "WIREPAD2,15/1,0"))
    )
    (comp (ref "H-5V")
      (value "0")
      (footprint "eagle-import:R0805")
      (libsource (lib "eagle-import") (part "R-EU_R0805"))
    )
    (comp (ref "H-12V")
      (value "0")
      (footprint "eagle-import:R0805")
      (libsource (lib "eagle-import") (part "R-EU_R0805"))
    )
    (comp (ref "HEAT_SWITCH+")
      (value "WIREPAD2,15/1,0")
      (footprint "eagle-import:2,15_1,0")
      (libsource (lib "eagle-import") (part "WIREPAD2,15/1,0"))
    )
    (comp (ref "HEAT_SWITCH_GND")
      (value "WIREPAD2,15/1,0")
      (footprint "eagle-import:2,15_1,0")
      (libsource (lib "eagle-import") (part "WIREPAD2,15/1,0"))
    )
    (comp (ref "R24")
      (value "255")
      (footprint "eagle-import:R0805")
      (libsource (lib "eagle-import") (part "R-EU_R0805"))
    )
    (comp (ref "R25")
      (value "10k")
      (footprint "eagle-import:R0603")
      (libsource (lib "eagle-import") (part "R-EU_R0603"))
    )
    (comp (ref "R26")
      (value "10k")
      (footprint "eagle-import:R0603")
      (libsource (lib "eagle-import") (part "R-EU_R0603"))
    )
    (comp (ref "R27")
      (value "4.7k")
      (footprint "eagle-import:R0603")
      (libsource (lib "eagle-import") (part "R-EU_R0603"))
    )
    (comp (ref "R28")
      (value "255")
      (footprint "eagle-import:R0805")
      (libsource (lib "eagle-import") (part "R-EU_R0805"))
    )
    (comp (ref "R29")
      (value "10k")
      (footprint "eagle-import:R0603")
      (libsource (lib "eagle-import") (part "R-EU_R0603"))
    )
    (comp (ref "R30")
      (value "10k")
      (footprint "eagle-import:R0603")
      (libsource (lib "eagle-import") (part "R-EU_R0603"))
    )
    (comp (ref "R31")
      (value "4.7k")
      (footprint "eagle-import:R0603")
      (libsource (lib "eagle-import") (part "R-EU_R0603"))
    )
    (comp (ref "R40")
      (value "255")
      (footprint "eagle-import:R0805")
      (libsource (lib "eagle-import") (part "R-EU_R0805"))
    )
    (comp (ref "R41")
      (value "10k")
      (footprint "eagle-import:R0603")
      (libsource (lib "eagle-import") (part "R-EU_R0603"))
    )
    (comp (ref "R42")
      (value "10k")
      (footprint "eagle-import:R0603")
      (libsource (lib "eagle-import") (part "R-EU_R0603"))
    )
    (comp (ref "R43")
      (value "4.7k")
      (footprint "eagle-import:R0603")
      (libsource (lib "eagle-import") (part "R-EU_R0603"))
    )
    (comp (ref "U4")
      (value "IRLML6344TRPBF")
      (footprint "eagle-import:SOT95P240X112-3N")
      (libsource (lib "eagle-import") (part "IRLML6344TRPBF"))
    )
    (comp (ref "U5")
      (value "IRLML6344TRPBF")
      (footprint "eagle-import:SOT95P240X112-3N")
      (libsource (lib "eagle-import") (part "IRLML6344TRPBF"))
    )
    (comp (ref "U6")
      (value "IRLML6344TRPBF")
      (footprint "eagle-import:SOT95P240X112-3N")
      (libsource (lib "eagle-import") (part "IRLML6344TRPBF"))
    )
    (comp (ref "U11")
      (value "IRLML6344TRPBF")
      (footprint "eagle-import:SOT95P240X112-3N")
      (libsource (lib "eagle-import") (part "IRLML6344TRPBF"))
    )
    (comp (ref "U12")
      (value "IRLML6344TRPBF")
      (footprint "eagle-import:SOT95P240X112-3N")
      (libsource (lib "eagle-import") (part "IRLML6344TRPBF"))
    )
  )
  (nets
    (net (code "1") (name "+3V3") (class "Default")
      (node (ref "DHT-EXT_3V3") (pin "1") (pinfunction "P_1") (pintype "passive"))
      (node (ref "DHT-INT_3V3") (pin "1") (pinfunction "P_1") (pintype "passive"))
      (node (ref "LIGHTSEN_3V3") (pin "1") (pinfunction "P_1") (pintype "passive"))
      (node (ref "OPTSEN-REC_3V3") (pin "1") (pinfunction "P_1") (pintype "passive"))
      (node (ref "R10") (pin "1") (pinfunction "1_1") (pintype "passive"))
      (node (ref "R12") (pin "3") (pinfunction "3_3") (pintype "passive"))
      (node (ref "R4") (pin "2") (pinfunction "2_2") (pintype "passive"))
      (node (ref "R9") (pin "1") (pinfunction "1_1") (pintype "passive"))
      (node (ref "SV1") (pin "1") (pinfunction "1_1") (pintype "passive"))
      (node (ref "SV1") (pin "17") (pinfunction "17_17") (pintype "passive"))
      (node (ref "U8") (pin "1") (pinfunction "G_1") (pintype "passive"))
      (node (ref "X2") (pin "6") (pinfunction "6_6") (pintype "passive"))
      (node (ref "X3") (pin "12") (pinfunction "12_12") (pintype "passive"))
      (node (ref "X3") (pin "17") (pinfunction "17_17") (pintype "passive"))
      (node (ref "X3") (pin "23") (pinfunction "23_23") (pintype "passive"))
      (node (ref "X3") (pin "8") (pinfunction "8_8") (pintype "passive"))
    )
    (net (code "2") (name "+5V") (class "Default")
      (node (ref "C20") (pin "1") (pinfunction "1_1") (pintype "passive"))
      (node (ref "C22") (pin "1") (pinfunction "1_1") (pintype "passive"))
      (node (ref "C23") (pin "1") (pinfunction "1_1") (pintype "passive"))
      (node (ref "D-5V") (pin "1") (pinfunction "1_1") (pintype "passive"))
      (node (ref "F-5V") (pin "1") (pinfunction "1_1") (pintype "passive"))
      (node (ref "H-5V") (pin "1") (pinfunction "1_1") (pintype "passive"))
      (node (ref "OPTSEN-EMIT_5V") (pin "1") (pinfunction "P_1") (pintype "passive"))
      (node (ref "R13") (pin "2") (pinfunction "2_2") (pintype "passive"))
      (node (ref "R34") (pin "2") (pinfunction "2_2") (pintype "passive"))
      (node (ref "SERVO_5V") (pin "1") (pinfunction "P_1") (pintype "passive"))
      (node (ref "SPM6530-1") (pin "P$2") (pinfunction "P$2_P$2") (pintype "passive"))
      (node (ref "SV1") (pin "2") (pinfunction "2_2") (pintype "passive"))
      (node (ref "SV1") (pin "4") (pinfunction "4_4") (pintype "passive"))
      (node (ref "U7") (pin "P$1") (pinfunction "VO_P$1") (pintype "bidirectional"))
      (node (ref "X3") (pin "10") (pinfunction "10_10") (pintype "passive"))
      (node (ref "X3") (pin "19") (pinfunction "19_19") (pintype "passive"))
      (node (ref "X3") (pin "21") (pinfunction "21_21") (pintype "passive"))
      (node (ref "X3") (pin "25") (pinfunction "25_25") (pintype "passive"))
      (node (ref "X3") (pin "4") (pinfunction "4_4") (pintype "passive"))
      (node (ref "X3") (pin "6") (pinfunction "6_6") (pintype "passive"))
    )
    (net (code "3") (name "+12V") (class "Default")
      (node (ref "BUZZER+") (pin "1") (pinfunction "P_1") (pintype "passive"))
      (node (ref "D-12V") (pin "1") (pinfunction "1_1") (pintype "passive"))
      (node (ref "D1") (pin "1") (pinfunction "A_1") (pintype "passive"))
      (node (ref "D3") (pin "1") (pinfunction "A_1") (pintype "passive"))
      (node (ref "F-12V") (pin "1") (pinfunction "1_1") (pintype "passive"))
      (node (ref "H-12V") (pin "1") (pinfunction "1_1") (pintype "passive"))
      (node (ref "POWER+") (pin "1") (pinfunction "P_1") (pintype "passive"))
      (node (ref "R2") (pin "2") (pinfunction "2_2") (pintype "passive"))
      (node (ref "T2") (pin "3") (pinfunction "VIN_3") (pintype "input"))
    )
    (net (code "4") (name "BUZZER") (class "Default")
      (node (ref "R39") (pin "2") (pinfunction "2_2") (pintype "passive"))
      (node (ref "SV1") (pin "37") (pinfunction "37_37") (pintype "passive"))
      (node (ref "U10") (pin "1") (pinfunction "G_1") (pintype "passive"))
    )
    (net (code "5") (name "DEHUM_LED") (class "Default")
      (node (ref "R40") (pin "2") (pinfunction "2_2") (pintype "passive"))
      (node (ref "X3") (pin "9") (pinfunction "9_9") (pintype "passive"))
    )
    (net (code "6") (name "DEHUM_LEVER_F") (class "Default")
      (node (ref "C1") (pin "1") (pinfunction "1_1") (pintype "passive"))
      (node (ref "R42") (pin "1") (pinfunction "1_1") (pintype "passive"))
      (node (ref "R43") (pin "1") (pinfunction "1_1") (pintype "passive"))
      (node (ref "SV1") (pin "32") (pinfunction "32_32") (pintype "passive"))
      (node (ref "U12") (pin "1") (pinfunction "G_1") (pintype "passive"))
    )
    (net (code "7") (name "DEHUM_LEVER_IN") (class "Default")
      (node (ref "R43") (pin "2") (pinfunction "2_2") (pintype "passive"))
      (node (ref "X3") (pin "11") (pinfunction "11_11") (pintype "passive"))
    )
    (net (code "8") (name "DEHUM_SWITCH") (class "Default")
      (node (ref "R41") (pin "1") (pinfunction "1_1") (pintype "passive"))
      (node (ref "SV1") (pin "31") (pinfunction "31_31") (pintype "passive"))
      (node (ref "U11") (pin "1") (pinfunction "G_1") (pintype "passive"))
    )
    (net (code "9") (name "DHT22_EXT") (class "Default")
      (node (ref "DHT-EXT_SIG") (pin "1") (pinfunction "P_1") (pintype "passive"))
      (node (ref "R10") (pin "2") (pinfunction "2_2") (pintype "passive"))
      (node (ref "SV1") (pin "11") (pinfunction "11_11") (pintype "passive"))
    )
    (net (code "10") (name "DHT22_INT") (class "Default")
      (node (ref "DHT-INT_SIG") (pin "1") (pinfunction "P_1") (pintype "passive"))
      (node (ref "R9") (pin "2") (pinfunction "2_2") (pintype "passive"))
      (node (ref "SV1") (pin "7") (pinfunction "7_7") (pintype "passive"))
    )
    (net (code "11") (name "EEPROM_SC") (class "Default")
      (node (ref "SV1") (pin "28") (pinfunction "28_28") (pintype "passive"))
    )
    (net (code "12") (name "EEPROM_SD") (class "Default")
      (node (ref "SV1") (pin "27") (pinfunction "27_27") (pintype "passive"))
    )
    (net (code "13") (name "ENABLE") (class "Default")
      (node (ref "R17") (pin "1") (pinfunction "1_1") (pintype "passive"))
      (node (ref "T3") (pin "C") (pinfunction "C_C") (pintype "passive"))
      (node (ref "U7") (pin "P$7") (pinfunction "EN_P$7") (pintype "bidirectional"))
    )
    (net (code "14") (name "FAN_LED") (class "Default")
      (node (ref "R28") (pin "2") (pinfunction "2_2") (pintype "passive"))
      (node (ref "X3") (pin "13") (pinfunction "13_13") (pintype "passive"))
    )
    (net (code "15") (name "FAN_LEVER_F") (class "Default")
      (node (ref "C8") (pin "1") (pinfunction "1_1") (pintype "passive"))
      (node (ref "R30") (pin "1") (pinfunction "1_1") (pintype "passive"))
      (node (ref "R31") (pin "1") (pinfunction "1_1") (pintype "passive"))
      (node (ref "SV1") (pin "35") (pinfunction "35_35") (pintype "passive"))
    )
    (net (code "16") (name "FAN_LEVER_IN") (class "Default")
      (node (ref "R31") (pin "2") (pinfunction "2_2") (pintype "passive"))
      (node (ref "X3") (pin "24") (pinfunction "24_24") (pintype "passive"))
    )
    (net (code "17") (name "FAN_SWITCH") (class "Default")
      (node (ref "R29") (pin "1") (pinfunction "1_1") (pintype "passive"))
      (node (ref "SV1") (pin "33") (pinfunction "33_33") (pintype "passive"))
      (node (ref "U6") (pin "1") (pinfunction "G_1") (pintype "passive"))
    )
    (net (code "18") (name "GND") (class "Default")
      (node (ref "C1") (pin "2") (pinfunction "2_2") (pintype "passive"))
      (node (ref "C10") (pin "2") (pinfunction "2_2") (pintype "passive"))
      (node (ref "C11") (pin "2") (pinfunction "2_2") (pintype "passive"))
      (node (ref "C15") (pin "-") (pinfunction "-_-") (pintype "passive"))
      (node (ref "C16") (pin "2") (pinfunction "2_2") (pintype "passive"))
      (node (ref "C17") (pin "2") (pinfunction "2_2") (pintype "passive"))
      (node (ref "C18") (pin "2") (pinfunction "2_2") (pintype "passive"))
      (node (ref "C19") (pin "2") (pinfunction "2_2") (pintype "passive"))
      (node (ref "C22") (pin "2") (pinfunction "2_2") (pintype "passive"))
      (node (ref "C23") (pin "2") (pinfunction "2_2") (pintype "passive"))
      (node (ref "C4") (pin "2") (pinfunction "2_2") (pintype "passive"))
      (node (ref "C5") (pin "-") (pinfunction "-_-") (pintype "passive"))
      (node (ref "C6") (pin "2") (pinfunction "2_2") (pintype "passive"))
      (node (ref "C7") (pin "2") (pinfunction "2_2") (pintype "passive"))
      (node (ref "C8") (pin "2") (pinfunction "2_2") (pintype "passive"))
      (node (ref "C9") (pin "2") (pinfunction "2_2") (pintype "passive"))
      (node (ref "DHT-EXT_GND") (pin "1") (pinfunction "P_1") (pintype "passive"))
      (node (ref "DHT-INT_GND") (pin "1") (pinfunction "P_1") (pintype "passive"))
      (node (ref "POWER-") (pin "1") (pinfunction "P_1") (pintype "passive"))
      (node (ref "R1") (pin "1") (pinfunction "1_1") (pintype "passive"))
      (node (ref "R11") (pin "1") (pinfunction "1_1") (pintype "passive"))
      (node (ref "R16") (pin "2") (pinfunction "2_2") (pintype "passive"))
      (node (ref "R21") (pin "1") (pinfunction "1_1") (pintype "passive"))
      (node (ref "R25") (pin "2") (pinfunction "2_2") (pintype "passive"))
      (node (ref "R26") (pin "2") (pinfunction "2_2") (pintype "passive"))
      (node (ref "R29") (pin "2") (pinfunction "2_2") (pintype "passive"))
      (node (ref "R3") (pin "1") (pinfunction "1_1") (pintype "passive"))
      (node (ref "R30") (pin "2") (pinfunction "2_2") (pintype "passive"))
      (node (ref "R35") (pin "1") (pinfunction "1_1") (pintype "passive"))
      (node (ref "R36") (pin "1") (pinfunction "1_1") (pintype "passive"))
      (node (ref "R37") (pin "2") (pinfunction "2_2") (pintype "passive"))
      (node (ref "R39") (pin "1") (pinfunction "1_1") (pintype "passive"))
      (node (ref "R41") (pin "2") (pinfunction "2_2") (pintype "passive"))
      (node (ref "R42") (pin "2") (pinfunction "2_2") (pintype "passive"))
      (node (ref "R8") (pin "1") (pinfunction "1_1") (pintype "passive"))
      (node (ref "SV1") (pin "14") (pinfunction "14_14") (pintype "passive"))
      (node (ref "SV1") (pin "20") (pinfunction "20_20") (pintype "passive"))
      (node (ref "SV1") (pin "25") (pinfunction "25_25") (pintype "passive"))
      (node (ref "SV1") (pin "30") (pinfunction "30_30") (pintype "passive"))
      (node (ref "SV1") (pin "34") (pinfunction "34_34") (pintype "passive"))
      (node (ref "SV1") (pin "39") (pinfunction "39_39") (pintype "passive"))
      (node (ref "SV1") (pin "6") (pinfunction "6_6") (pintype "passive"))
      (node (ref "SV1") (pin "9") (pinfunction "9_9") (pintype "passive"))
      (node (ref "T2") (pin "2") (pinfunction "GND_2") (pintype "power_in"))
      (node (ref "T2") (pin "4") (pinfunction "GND_4") (pintype "power_in"))
      (node (ref "T3") (pin "E") (pinfunction "E_E") (pintype "passive"))
      (node (ref "T4") (pin "E") (pinfunction "E_E") (pintype "passive"))
      (node (ref "U1") (pin "2") (pinfunction "S_2") (pintype "passive"))
      (node (ref "U10") (pin "2") (pinfunction "S_2") (pintype "passive"))
      (node (ref "U11") (pin "2") (pinfunction "S_2") (pintype "passive"))
      (node (ref "U12") (pin "2") (pinfunction "S_2") (pintype "passive"))
      (node (ref "U2") (pin "1-GND") (pinfunction "GND_1-GND") (pintype "passive"))
      (node (ref "U3") (pin "2") (pinfunction "S_2") (pintype "passive"))
      (node (ref "U4") (pin "2") (pinfunction "S_2") (pintype "passive"))
      (node (ref "U5") (pin "2") (pinfunction "S_2") (pintype "passive"))
      (node (ref "U6") (pin "2") (pinfunction "S_2") (pintype "passive"))
      (node (ref "U7") (pin "P$15") (pinfunction "GND_P$15") (pintype "bidirectional"))
      (node (ref "U7") (pin "P$5") (pinfunction "GND_P$5") (pintype "bidirectional"))
      (node (ref "U7") (pin "P$8") (pinfunction "GND_P$8") (pintype "bidirectional"))
      (node (ref "U7") (pin "P$9") (pinfunction "GND_P$9") (pintype "bidirectional"))
      (node (ref "U9") (pin "2") (pinfunction "S_2") (pintype "passive"))
      (node (ref "X2") (pin "1") (pinfunction "1_1") (pintype "passive"))
      (node (ref "X2") (pin "5") (pinfunction "5_5") (pintype "passive"))
      (node (ref "X3") (pin "1") (pinfunction "1_1") (pintype "passive"))
      (node (ref "X3") (pin "14") (pinfunction "14_14") (pintype "passive"))
      (node (ref "X3") (pin "15") (pinfunction "15_15") (pintype "passive"))
      (node (ref "X3") (pin "16") (pinfunction "16_16") (pintype "passive"))
    )
    (net (code "19") (name "HEAT_LED") (class "Default")
      (node (ref "R24") (pin "2") (pinfunction "2_2") (pintype "passive"))
      (node (ref "X3") (pin "5") (pinfunction "5_5") (pintype "passive"))
    )
    (net (code "20") (name "HEAT_LEVER_F") (class "Default")
      (node (ref "C7") (pin "1") (pinfunction "1_1") (pintype "passive"))
      (node (ref "R26") (pin "1") (pinfunction "1_1") (pintype "passive"))
      (node (ref "R27") (pin "1") (pinfunction "1_1") (pintype "passive"))
      (node (ref "SV1") (pin "29") (pinfunction "29_29") (pintype "passive"))
      (node (ref "U5") (pin "1") (pinfunction "G_1") (pintype "passive"))
    )
    (net (code "21") (name "HEAT_LEVER_IN") (class "Default")
      (node (ref "R27") (pin "2") (pinfunction "2_2") (pintype "passive"))
      (node (ref "X3") (pin "7") (pinfunction "7_7") (pintype "passive"))
    )
    (net (code "22") (name "HEAT_SWITCH") (class "Default")
      (node (ref "R25") (pin "1") (pinfunction "1_1") (pintype "passive"))
      (node (ref "SV1") (pin "22") (pinfunction "22_22") (pintype "passive"))
      (node (ref "U4") (pin "1") (pinfunction "G_1") (pintype "passive"))
    )
    (net (code "23") (name "I2C_SCL") (class "Default")
      (node (ref "SV1") (pin "5") (pinfunction "5_5") (pintype "passive"))
      (node (ref "X2") (pin "3") (pinfunction "3_3") (pintype "passive"))
    )
    (net (code "24") (name "I2C_SDA") (class "Default")
      (node (ref "SV1") (pin "3") (pinfunction "3_3") (pintype "passive"))
      (node (ref "X2") (pin "2") (pinfunction "2_2") (pintype "passive"))
    )
    (net (code "25") (name "LED_ON_GND") (class "Default")
      (node (ref "R36") (pin "2") (pinfunction "2_2") (pintype "passive"))
      (node (ref "X3") (pin "22") (pinfunction "22_22") (pintype "passive"))
    )
    (net (code "26") (name "LED_RUN") (class "Default")
      (node (ref "R37") (pin "1") (pinfunction "1_1") (pintype "passive"))
      (node (ref "SV1") (pin "36") (pinfunction "36_36") (pintype "passive"))
      (node (ref "U9") (pin "1") (pinfunction "G_1") (pintype "passive"))
    )
    (net (code "27") (name "LED_RUN_GND") (class "Default")
      (node (ref "R38") (pin "2") (pinfunction "2_2") (pintype "passive"))
      (node (ref "X3") (pin "20") (pinfunction "20_20") (pintype "passive"))
    )
    (net (code "28") (name "LIGHT_SENSOR") (class "Default")
      (node (ref "C16") (pin "1") (pinfunction "1_1") (pintype "passive"))
      (node (ref "R5") (pin "1") (pinfunction "1_1") (pintype "passive"))
      (node (ref "SV1") (pin "18") (pinfunction "18_18") (pintype "passive"))
    )
    (net (code "29") (name "Net-(BUZZER--P)") (class "Default")
      (node (ref "BUZZER-") (pin "1") (pinfunction "P_1") (pintype "passive"))
      (node (ref "U10") (pin "3") (pinfunction "D_3") (pintype "passive"))
    )
    (net (code "30") (name "Net-(C2-Pad-)") (class "Default")
      (node (ref "C2") (pin "-") (pinfunction "-_-") (pintype "passive"))
      (node (ref "C3") (pin "+") (pinfunction "+_+") (pintype "passive"))
    )
    (net (code "31") (name "Net-(C12-Pad+)") (class "Default")
      (node (ref "C12") (pin "+") (pinfunction "+_+") (pintype "passive"))
      (node (ref "C3") (pin "-") (pinfunction "-_-") (pintype "passive"))
    )
    (net (code "32") (name "Net-(C12-Pad-)") (class "Default")
      (node (ref "C12") (pin "-") (pinfunction "-_-") (pintype "passive"))
      (node (ref "C13") (pin "+") (pinfunction "+_+") (pintype "passive"))
    )
    (net (code "33") (name "Net-(C13-Pad-)") (class "Default")
      (node (ref "C13") (pin "-") (pinfunction "-_-") (pintype "passive"))
      (node (ref "C14") (pin "+") (pinfunction "+_+") (pintype "passive"))
    )
    (net (code "34") (name "Net-(C14-Pad-)") (class "Default")
      (node (ref "C14") (pin "-") (pinfunction "-_-") (pintype "passive"))
      (node (ref "C15") (pin "+") (pinfunction "+_+") (pintype "passive"))
    )
    (net (code "35") (name "Net-(C21-Pad2)") (class "Default")
      (node (ref "C21") (pin "2") (pinfunction "2_2") (pintype "passive"))
      (node (ref "SPM6530-1") (pin "P$1") (pinfunction "P$1_P$1") (pintype "passive"))
      (node (ref "U7") (pin "P$10") (pinfunction "SW_P$10") (pintype "bidirectional"))
      (node (ref "U7") (pin "P$11") (pinfunction "SW_P$11") (pintype "bidirectional"))
    )
    (net (code "36") (name "Net-(D1-C)") (class "Default")
      (node (ref "D1") (pin "3") (pinfunction "C_3") (pintype "passive"))
      (node (ref "SMW5-1") (pin "P$1") (pinfunction "1_P$1") (pintype "passive"))
      (node (ref "SMW5-2") (pin "P$1") (pinfunction "1_P$1") (pintype "passive"))
    )
    (net (code "37") (name "Net-(D2-A)") (class "Default")
      (node (ref "C2") (pin "+") (pinfunction "+_+") (pintype "passive"))
      (node (ref "D2") (pin "1") (pinfunction "A_1") (pintype "passive"))
      (node (ref "SMW5-1") (pin "P$2") (pinfunction "2_P$2") (pintype "passive"))
      (node (ref "SMW5-2") (pin "P$2") (pinfunction "2_P$2") (pintype "passive"))
    )
    (net (code "38") (name "Net-(D4-A)") (class "Default")
      (node (ref "D4") (pin "1") (pinfunction "A_1") (pintype "passive"))
      (node (ref "R6") (pin "1") (pinfunction "1_1") (pintype "passive"))
      (node (ref "R7") (pin "2") (pinfunction "2_2") (pintype "passive"))
      (node (ref "U2") (pin "7-DIS") (pinfunction "DISCH_7-DIS") (pintype "output"))
    )
    (net (code "39") (name "Net-(D4-C)") (class "Default")
      (node (ref "C5") (pin "+") (pinfunction "+_+") (pintype "passive"))
      (node (ref "D4") (pin "3") (pinfunction "C_3") (pintype "passive"))
      (node (ref "R7") (pin "1") (pinfunction "1_1") (pintype "passive"))
      (node (ref "U2") (pin "2-TRIG") (pinfunction "TRIG_2-TRIG") (pintype "input"))
      (node (ref "U2") (pin "6-THR") (pinfunction "THRES_6-THR") (pintype "passive"))
    )
    (net (code "40") (name "Net-(D5-A)") (class "Default")
      (node (ref "D5") (pin "1") (pinfunction "A_1") (pintype "passive"))
      (node (ref "HEAT_SWITCH_GND") (pin "1") (pinfunction "P_1") (pintype "passive"))
      (node (ref "R24") (pin "1") (pinfunction "1_1") (pintype "passive"))
      (node (ref "U4") (pin "3") (pinfunction "D_3") (pintype "passive"))
      (node (ref "U5") (pin "3") (pinfunction "D_3") (pintype "passive"))
    )
    (net (code "41") (name "Net-(D5-C)") (class "Default")
      (node (ref "D5") (pin "3") (pinfunction "C_3") (pintype "passive"))
      (node (ref "H-12V") (pin "2") (pinfunction "2_2") (pintype "passive"))
      (node (ref "H-5V") (pin "2") (pinfunction "2_2") (pintype "passive"))
      (node (ref "HEAT_SWITCH+") (pin "1") (pinfunction "P_1") (pintype "passive"))
    )
    (net (code "42") (name "Net-(D6-A)") (class "Default")
      (node (ref "D6") (pin "1") (pinfunction "A_1") (pintype "passive"))
      (node (ref "DEHUM_SWITCH_GND") (pin "1") (pinfunction "P_1") (pintype "passive"))
      (node (ref "R40") (pin "1") (pinfunction "1_1") (pintype "passive"))
      (node (ref "U11") (pin "3") (pinfunction "D_3") (pintype "passive"))
      (node (ref "U12") (pin "3") (pinfunction "D_3") (pintype "passive"))
    )
    (net (code "43") (name "Net-(D6-C)") (class "Default")
      (node (ref "D-12V") (pin "2") (pinfunction "2_2") (pintype "passive"))
      (node (ref "D-5V") (pin "2") (pinfunction "2_2") (pintype "passive"))
      (node (ref "D6") (pin "3") (pinfunction "C_3") (pintype "passive"))
      (node (ref "DEHUM_SWITCH+") (pin "1") (pinfunction "P_1") (pintype "passive"))
    )
    (net (code "44") (name "Net-(D7-A)") (class "Default")
      (node (ref "D7") (pin "1") (pinfunction "A_1") (pintype "passive"))
      (node (ref "FAN_SWITCH_GND") (pin "1") (pinfunction "P_1") (pintype "passive"))
      (node (ref "R28") (pin "1") (pinfunction "1_1") (pintype "passive"))
      (node (ref "U6") (pin "3") (pinfunction "D_3") (pintype "passive"))
    )
    (net (code "45") (name "Net-(D7-C)") (class "Default")
      (node (ref "D7") (pin "3") (pinfunction "C_3") (pintype "passive"))
      (node (ref "F-12V") (pin "2") (pinfunction "2_2") (pintype "passive"))
      (node (ref "F-5V") (pin "2") (pinfunction "2_2") (pintype "passive"))
      (node (ref "FAN_SWITCH+") (pin "1") (pinfunction "P_1") (pintype "passive"))
    )
    (net (code "46") (name "Net-(LIGHTSEN_SIG-P)") (class "Default")
      (node (ref "C17") (pin "1") (pinfunction "1_1") (pintype "passive"))
      (node (ref "LIGHTSEN_SIG") (pin "1") (pinfunction "P_1") (pintype "passive"))
      (node (ref "R14") (pin "2") (pinfunction "2_2") (pintype "passive"))
    )
    (net (code "47") (name "Net-(OPTSEN-EMIT_GND-P)") (class "Default")
      (node (ref "OPTSEN-EMIT_GND") (pin "1") (pinfunction "P_1") (pintype "passive"))
      (node (ref "R15") (pin "2") (pinfunction "2_2") (pintype "passive"))
    )
    (net (code "48") (name "Net-(R12-Pad1)") (class "Default")
      (node (ref "R12") (pin "1") (pinfunction "1_1") (pintype "passive"))
      (node (ref "R5") (pin "2") (pinfunction "2_2") (pintype "passive"))
      (node (ref "T4") (pin "C") (pinfunction "C_C") (pintype "passive"))
    )
    (net (code "49") (name "Net-(R14-Pad1)") (class "Default")
      (node (ref "R14") (pin "1") (pinfunction "1_1") (pintype "passive"))
      (node (ref "T4") (pin "B") (pinfunction "B_B") (pintype "passive"))
    )
    (net (code "50") (name "Net-(R19-Pad2)") (class "Default")
      (node (ref "R19") (pin "2") (pinfunction "2_2") (pintype "passive"))
      (node (ref "T3") (pin "B") (pinfunction "B_B") (pintype "passive"))
    )
    (net (code "51") (name "Net-(SERVO_GND-P)") (class "Default")
      (node (ref "SERVO_GND") (pin "1") (pinfunction "P_1") (pintype "passive"))
      (node (ref "U1") (pin "3") (pinfunction "D_3") (pintype "passive"))
    )
    (net (code "52") (name "Net-(T2-VOUT)") (class "Default")
      (node (ref "R18") (pin "1") (pinfunction "1_1") (pintype "passive"))
      (node (ref "T1") (pin "C") (pinfunction "C_C") (pintype "passive"))
      (node (ref "T2") (pin "1") (pinfunction "VOUT_1") (pintype "output"))
    )
    (net (code "53") (name "Net-(U2-CONT)") (class "Default")
      (node (ref "C6") (pin "1") (pinfunction "1_1") (pintype "passive"))
      (node (ref "U2") (pin "5-CONT") (pinfunction "CONT_5-CONT") (pintype "passive"))
    )
    (net (code "54") (name "Net-(U2-OUT)") (class "Default")
      (node (ref "R19") (pin "1") (pinfunction "1_1") (pintype "passive"))
      (node (ref "U2") (pin "3-OUT") (pinfunction "OUT_3-OUT") (pintype "output"))
    )
    (net (code "55") (name "Net-(U2-RESET)") (class "Default")
      (node (ref "R8") (pin "2") (pinfunction "2_2") (pintype "passive"))
      (node (ref "T1") (pin "E") (pinfunction "E_E") (pintype "passive"))
      (node (ref "U2") (pin "4-RESET") (pinfunction "RESET_4-RESET") (pintype "input"))
    )
    (net (code "56") (name "Net-(U3-D)") (class "Default")
      (node (ref "R15") (pin "1") (pinfunction "1_1") (pintype "passive"))
      (node (ref "U3") (pin "3") (pinfunction "D_3") (pintype "passive"))
    )
    (net (code "57") (name "Net-(U7-PG)") (class "Default")
      (node (ref "R32") (pin "2") (pinfunction "2_2") (pintype "passive"))
      (node (ref "U7") (pin "P$6") (pinfunction "PG_P$6") (pintype "bidirectional"))
    )
    (net (code "58") (name "Net-(U7-SS)") (class "Default")
      (node (ref "C19") (pin "1") (pinfunction "1_1") (pintype "passive"))
      (node (ref "U7") (pin "P$4") (pinfunction "SS_P$4") (pintype "bidirectional"))
    )
    (net (code "59") (name "Net-(U7-VBST)") (class "Default")
      (node (ref "C21") (pin "1") (pinfunction "1_1") (pintype "passive"))
      (node (ref "U7") (pin "P$12") (pinfunction "VBST_P$12") (pintype "bidirectional"))
    )
    (net (code "60") (name "Net-(U7-VFB)") (class "Default")
      (node (ref "C20") (pin "2") (pinfunction "2_2") (pintype "passive"))
      (node (ref "R34") (pin "1") (pinfunction "1_1") (pintype "passive"))
      (node (ref "R35") (pin "2") (pinfunction "2_2") (pintype "passive"))
      (node (ref "U7") (pin "P$2") (pinfunction "VFB_P$2") (pintype "bidirectional"))
    )
    (net (code "61") (name "Net-(U7-VREG5)") (class "Default")
      (node (ref "C18") (pin "1") (pinfunction "1_1") (pintype "passive"))
      (node (ref "R32") (pin "1") (pinfunction "1_1") (pintype "passive"))
      (node (ref "U7") (pin "P$3") (pinfunction "VREG5_P$3") (pintype "bidirectional"))
    )
    (net (code "62") (name "Net-(U9-D)") (class "Default")
      (node (ref "R38") (pin "1") (pinfunction "1_1") (pintype "passive"))
      (node (ref "U9") (pin "3") (pinfunction "D_3") (pintype "passive"))
    )
    (net (code "63") (name "OPTSEN_ON{slash}OFF") (class "Default")
      (node (ref "R16") (pin "1") (pinfunction "1_1") (pintype "passive"))
      (node (ref "SV1") (pin "15") (pinfunction "15_15") (pintype "passive"))
      (node (ref "U3") (pin "1") (pinfunction "G_1") (pintype "passive"))
    )
    (net (code "64") (name "OPTSEN_STATE") (class "Default")
      (node (ref "OPTSEN-REC_STATE") (pin "1") (pinfunction "P_1") (pintype "passive"))
      (node (ref "R11") (pin "2") (pinfunction "2_2") (pintype "passive"))
      (node (ref "SV1") (pin "16") (pinfunction "16_16") (pintype "passive"))
    )
    (net (code "65") (name "POWER_STATE") (class "Default")
      (node (ref "R2") (pin "1") (pinfunction "1_1") (pintype "passive"))
      (node (ref "R3") (pin "2") (pinfunction "2_2") (pintype "passive"))
      (node (ref "SV1") (pin "40") (pinfunction "40_40") (pintype "passive"))
    )
    (net (code "66") (name "RESET_LEVER") (class "Default")
      (node (ref "C4") (pin "1") (pinfunction "1_1") (pintype "passive"))
      (node (ref "SV1") (pin "26") (pinfunction "26_26") (pintype "passive"))
      (node (ref "X3") (pin "18") (pinfunction "18_18") (pintype "passive"))
    )
    (net (code "67") (name "SERVO_ON{slash}OFF") (class "Default")
      (node (ref "R1") (pin "2") (pinfunction "2_2") (pintype "passive"))
      (node (ref "SV1") (pin "13") (pinfunction "13_13") (pintype "passive"))
      (node (ref "U1") (pin "1") (pinfunction "G_1") (pintype "passive"))
    )
    (net (code "68") (name "SERVO_PWM") (class "Default")
      (node (ref "SERVO_PWM") (pin "1") (pinfunction "P_1") (pintype "passive"))
      (node (ref "SV1") (pin "12") (pinfunction "12_12") (pintype "passive"))
    )
    (net (code "69") (name "SPI_CE0") (class "Default")
      (node (ref "SV1") (pin "24") (pinfunction "24_24") (pintype "passive"))
      (node (ref "X2") (pin "4") (pinfunction "4_4") (pintype "passive"))
    )
    (net (code "70") (name "SPI_MISO") (class "Default")
      (node (ref "SV1") (pin "21") (pinfunction "21_21") (pintype "passive"))
      (node (ref "X2") (pin "8") (pinfunction "8_8") (pintype "passive"))
    )
    (net (code "71") (name "SPI_MOSI") (class "Default")
      (node (ref "SV1") (pin "19") (pinfunction "19_19") (pintype "passive"))
      (node (ref "X2") (pin "7") (pinfunction "7_7") (pintype "passive"))
    )
    (net (code "72") (name "SPI_SCLK") (class "Default")
      (node (ref "SV1") (pin "23") (pinfunction "23_23") (pintype "passive"))
      (node (ref "X2") (pin "9") (pinfunction "9_9") (pintype "passive"))
    )
    (net (code "73") (name "UART_RX_3V3") (class "Default")
      (node (ref "R20") (pin "1") (pinfunction "1_1") (pintype "passive"))
      (node (ref "R21") (pin "2") (pinfunction "2_2") (pintype "passive"))
      (node (ref "SV1") (pin "10") (pinfunction "10_10") (pintype "passive"))
    )
    (net (code "74") (name "UART_RX_5V") (class "Default")
      (node (ref "R20") (pin "2") (pinfunction "2_2") (pintype "passive"))
      (node (ref "X3") (pin "3") (pinfunction "3_3") (pintype "passive"))
    )
    (net (code "75") (name "UART_TX_3V3") (class "Default")
      (node (ref "R4") (pin "1") (pinfunction "1_1") (pintype "passive"))
      (node (ref "SV1") (pin "8") (pinfunction "8_8") (pintype "passive"))
      (node (ref "U8") (pin "2") (pinfunction "S_2") (pintype "passive"))
    )
    (net (code "76") (name "UART_TX_5V") (class "Default")
      (node (ref "R13") (pin "1") (pinfunction "1_1") (pintype "passive"))
      (node (ref "U8") (pin "3") (pinfunction "D_3") (pintype "passive"))
      (node (ref "X3") (pin "2") (pinfunction "2_2") (pintype "passive"))
    )
    (net (code "77") (name "VCOND") (class "Default")
      (node (ref "C10") (pin "1") (pinfunction "1_1") (pintype "passive"))
      (node (ref "C11") (pin "1") (pinfunction "1_1") (pintype "passive"))
      (node (ref "C9") (pin "1") (pinfunction "1_1") (pintype "passive"))
      (node (ref "D2") (pin "3") (pinfunction "C_3") (pintype "passive"))
      (node (ref "D3") (pin "3") (pinfunction "C_3") (pintype "passive"))
      (node (ref "R17") (pin "2") (pinfunction "2_2") (pintype "passive"))
      (node (ref "R6") (pin "2") (pinfunction "2_2") (pintype "passive"))
      (node (ref "U2") (pin "8-VDD") (pinfunction "VDD_8-VDD") (pintype "power_in"))
      (node (ref "U7") (pin "P$13") (pinfunction "VIN_P$13") (pintype "bidirectional"))
      (node (ref "U7") (pin "P$14") (pinfunction "VIN_P$14") (pintype "bidirectional"))
    )
    (net (code "78") (name "WATCHDOG") (class "Default")
      (node (ref "R18") (pin "2") (pinfunction "2_2") (pintype "passive"))
      (node (ref "SV1") (pin "38") (pinfunction "38_38") (pintype "passive"))
      (node (ref "T1") (pin "B") (pinfunction "B_B") (pintype "passive"))
    )
    (net (code "79") (name "unconnected-(R12-Pad2)") (class "Default")
      (node (ref "R12") (pin "2") (pinfunction "2_2") (pintype "passive"))
    )
  )
)
